# EEZ_CF-DIC_r3B7.net
KiCad netlist of a schematic drawn in EAGLE
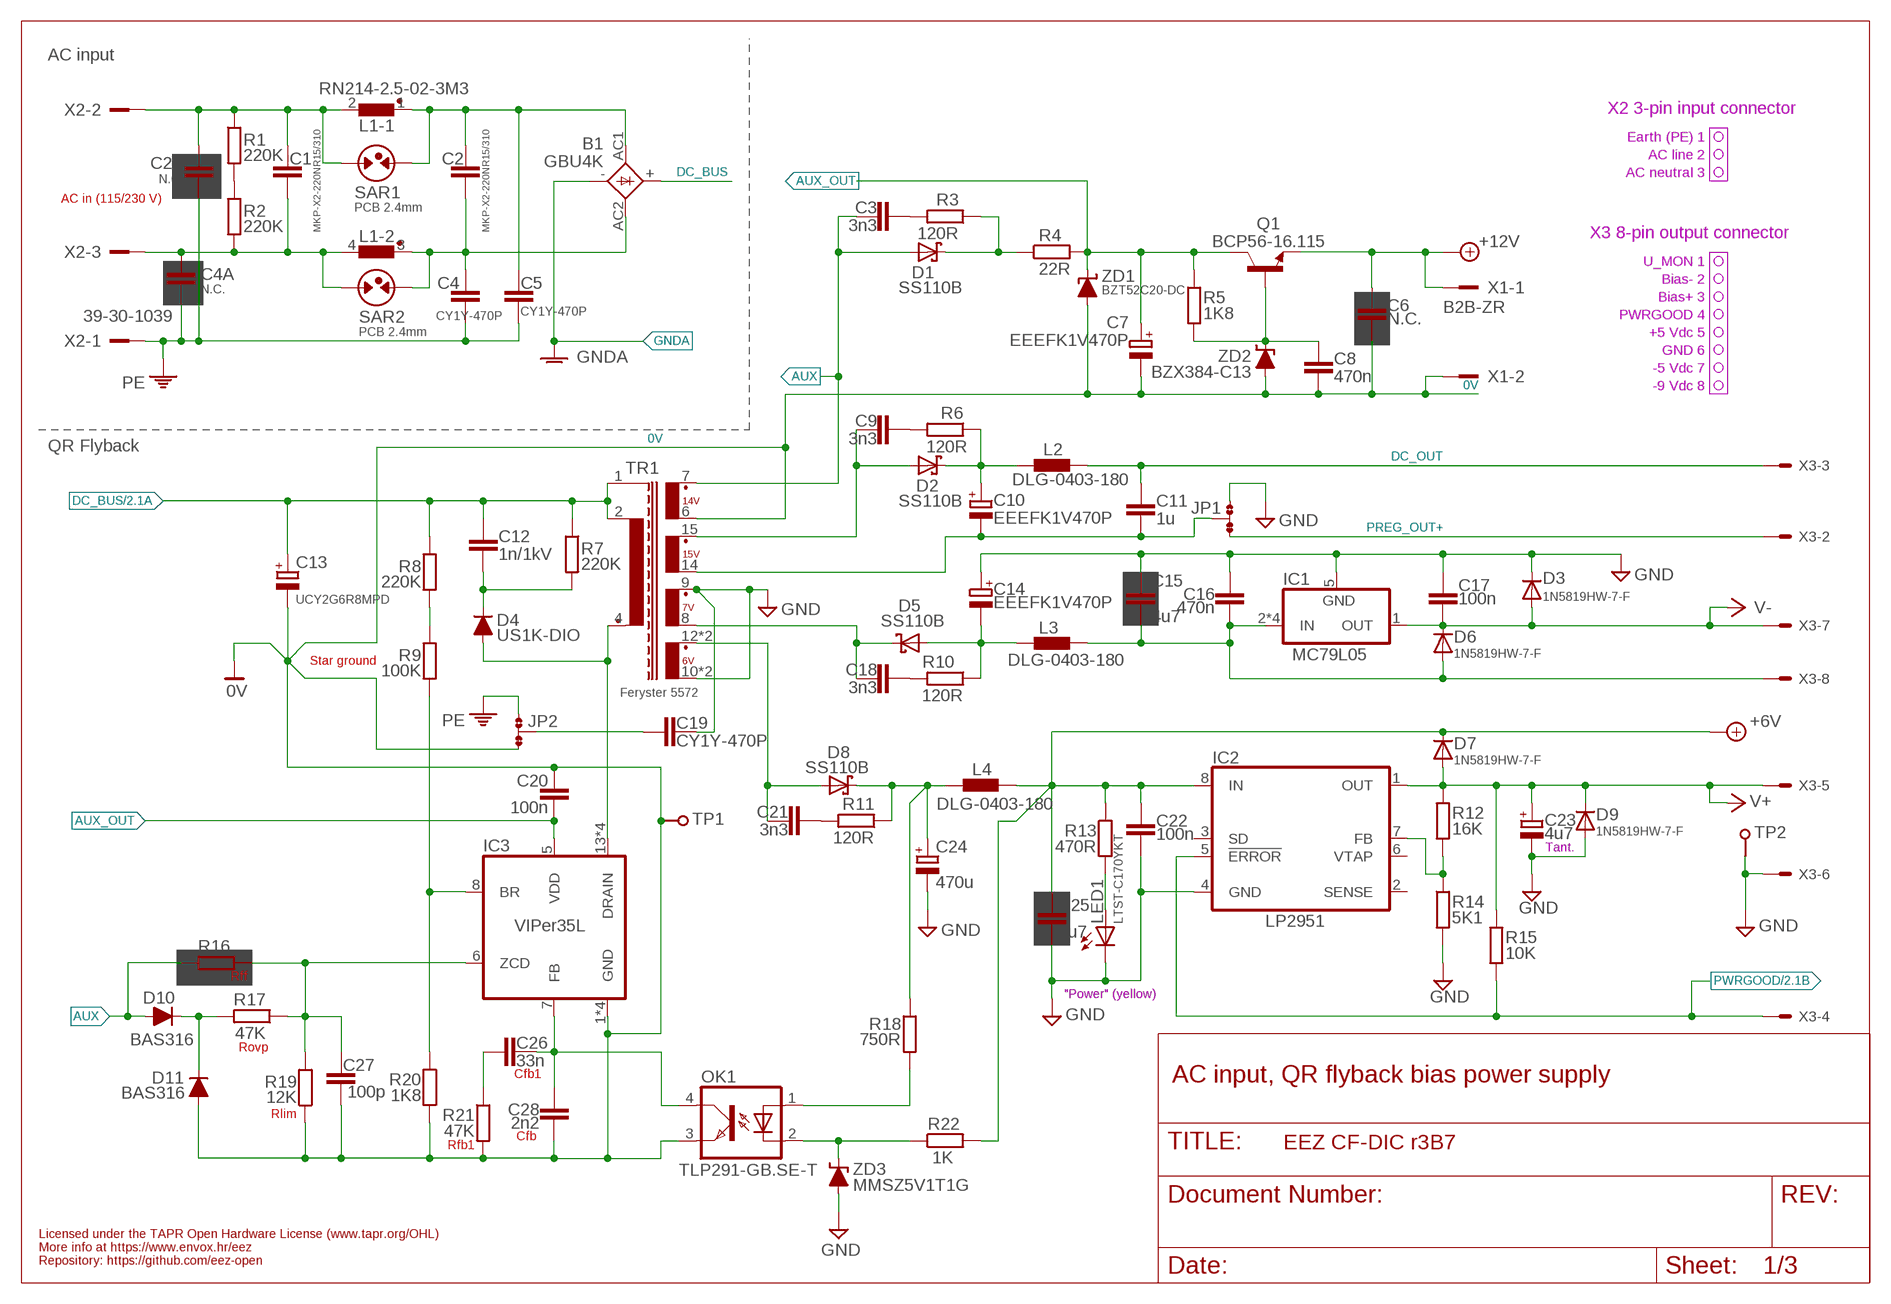
[diagram p0: schematic, sheet 1]
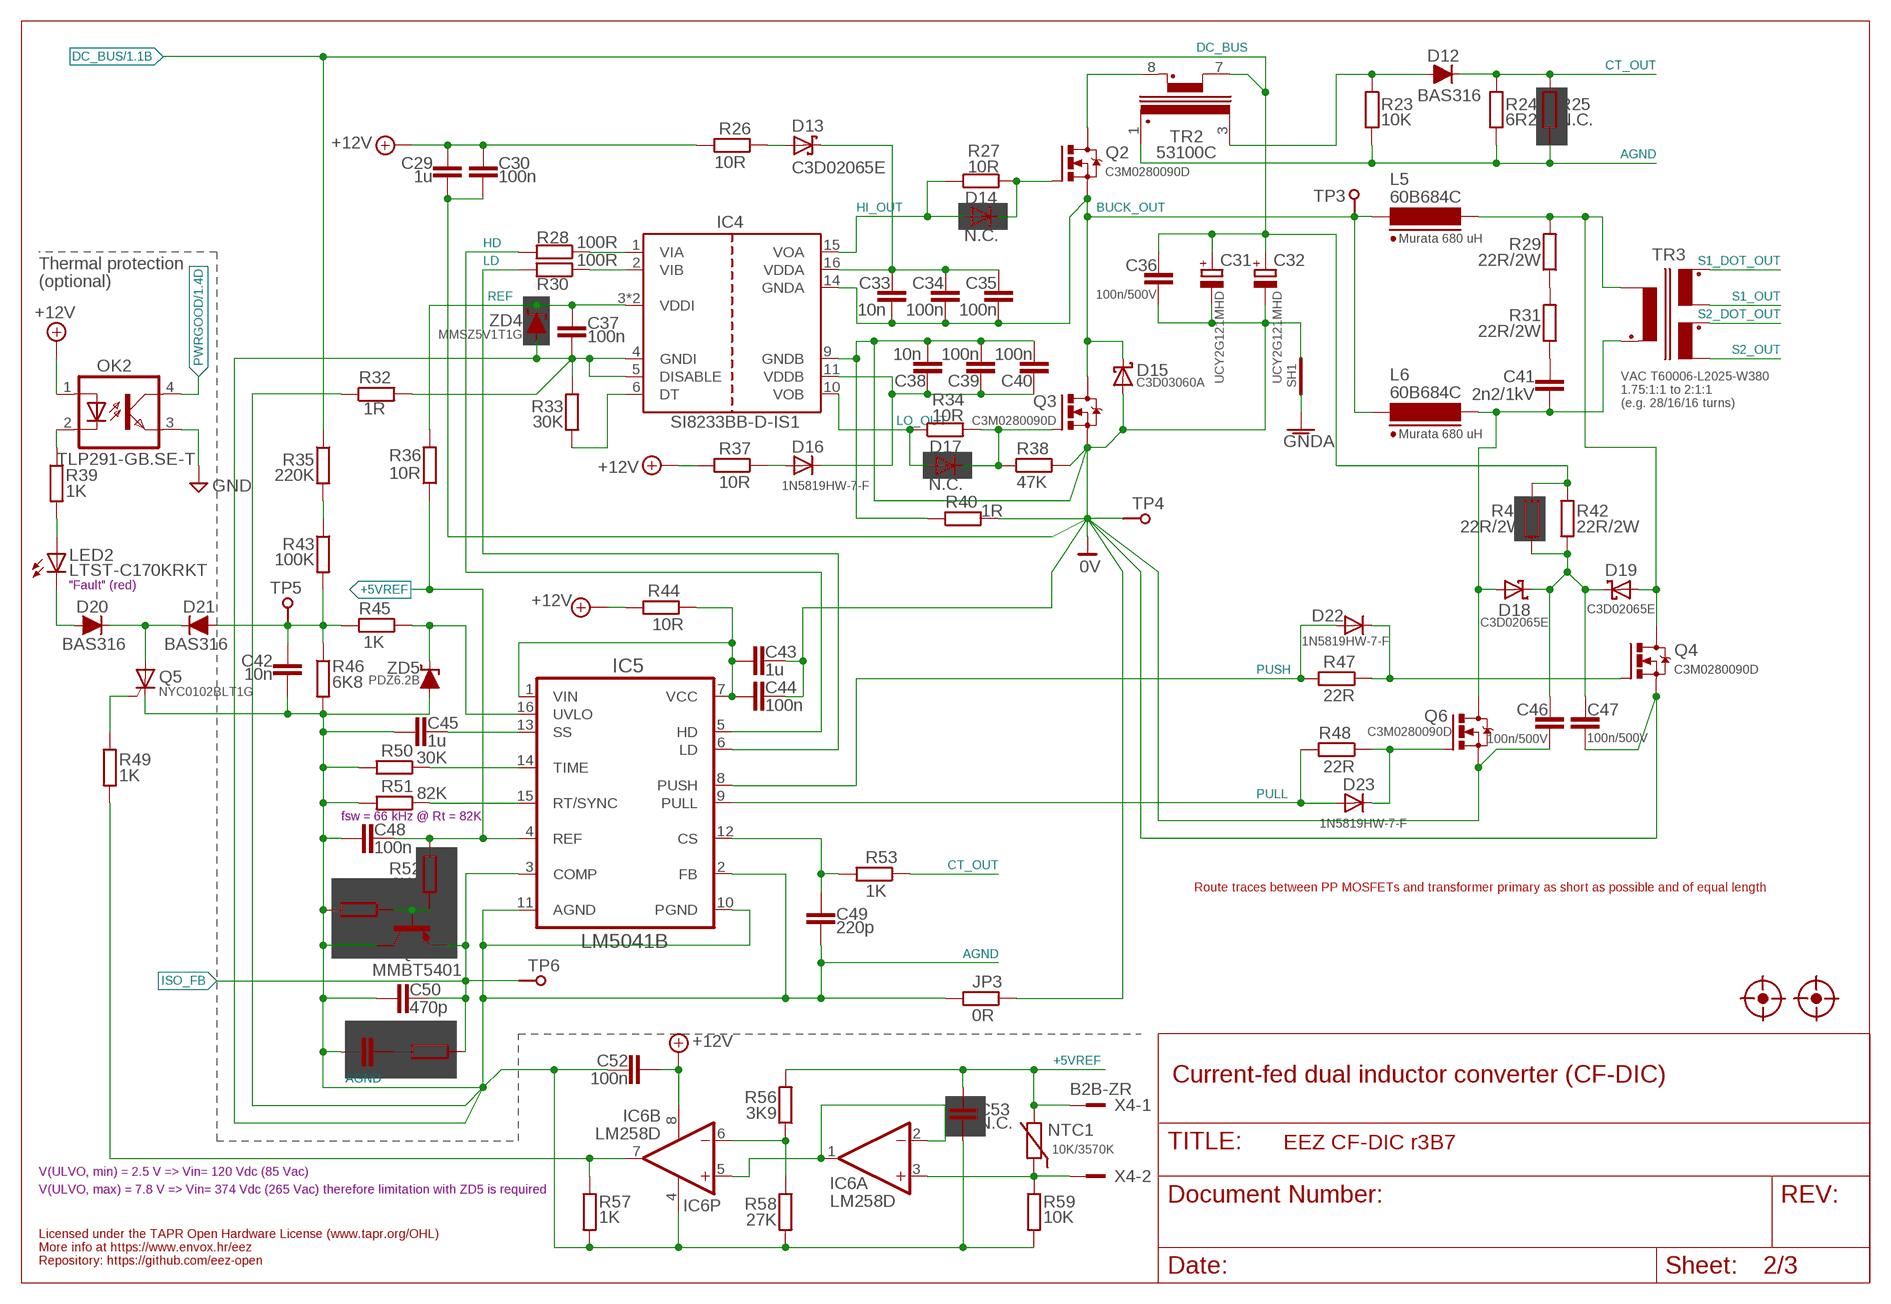
[diagram p1: schematic, sheet 2]
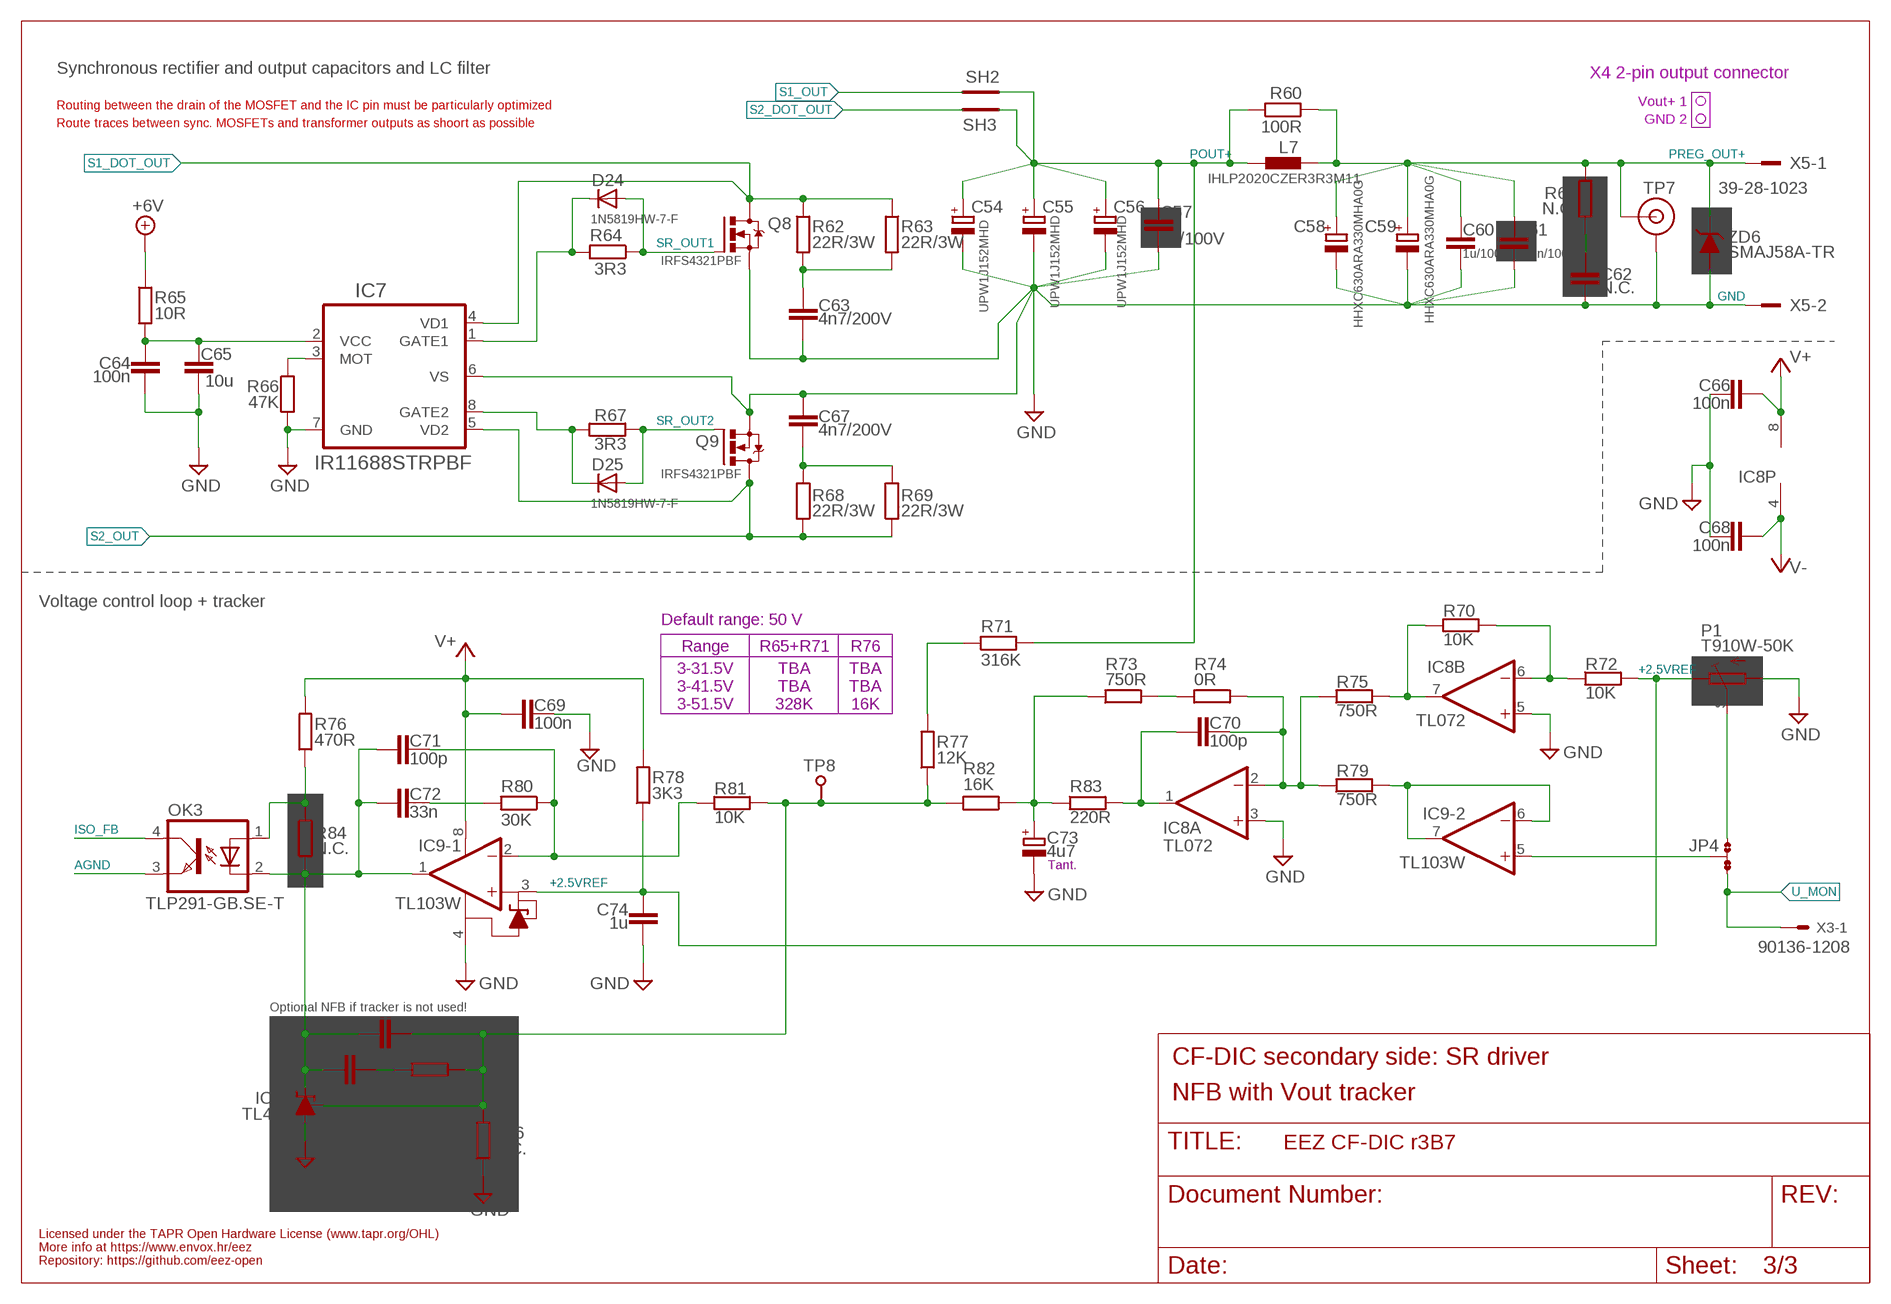
[diagram p2: schematic, sheet 3]

(export (version "E")
  (design (tool "Eeschema 10.0.6"))
  (components
    (comp (ref "C29")
      (value "1u")
      (footprint "eagle-import:C0805")
      (libsource (lib "eagle-import") (part "C-EUC0805"))
    )
    (comp (ref "C30")
      (value "100n")
      (footprint "eagle-import:C0603")
      (libsource (lib "eagle-import") (part "C-EUC0603"))
    )
    (comp (ref "C31")
      (value "UCY2G121MHD")
      (footprint "eagle-import:ECAP7.5_18")
      (libsource (lib "eagle-import") (part "ECAP7.5G_18MM"))
    )
    (comp (ref "C32")
      (value "UCY2G121MHD")
      (footprint "eagle-import:ECAP7.5_18")
      (libsource (lib "eagle-import") (part "ECAP7.5G_18MM"))
    )
    (comp (ref "C33")
      (value "10n")
      (footprint "eagle-import:C0603")
      (libsource (lib "eagle-import") (part "C-EUC0603"))
    )
    (comp (ref "C34")
      (value "100n")
      (footprint "eagle-import:C0603")
      (libsource (lib "eagle-import") (part "C-EUC0603"))
    )
    (comp (ref "C35")
      (value "100n")
      (footprint "eagle-import:C0603")
      (libsource (lib "eagle-import") (part "C-EUC0603"))
    )
    (comp (ref "C36")
      (value "100n/500V")
      (footprint "eagle-import:C1812")
      (libsource (lib "eagle-import") (part "C-EUC1812"))
    )
    (comp (ref "C37")
      (value "100n")
      (footprint "eagle-import:C0603")
      (libsource (lib "eagle-import") (part "C-EUC0603"))
    )
    (comp (ref "C38")
      (value "10n")
      (footprint "eagle-import:C0603")
      (libsource (lib "eagle-import") (part "C-EUC0603"))
    )
    (comp (ref "C39")
      (value "100n")
      (footprint "eagle-import:C0603")
      (libsource (lib "eagle-import") (part "C-EUC0603"))
    )
    (comp (ref "C40")
      (value "100n")
      (footprint "eagle-import:C0603")
      (libsource (lib "eagle-import") (part "C-EUC0603"))
    )
    (comp (ref "C41")
      (value "2n2/1kV")
      (footprint "eagle-import:C1210")
      (libsource (lib "eagle-import") (part "C-EUC1210"))
    )
    (comp (ref "C42")
      (value "10n")
      (footprint "eagle-import:C0603")
      (libsource (lib "eagle-import") (part "C-EUC0603"))
    )
    (comp (ref "C43")
      (value "1u")
      (footprint "eagle-import:C0805")
      (libsource (lib "eagle-import") (part "C-EUC0805"))
    )
    (comp (ref "C44")
      (value "100n")
      (footprint "eagle-import:C0603")
      (libsource (lib "eagle-import") (part "C-EUC0603"))
    )
    (comp (ref "C45")
      (value "1u")
      (footprint "eagle-import:C0805")
      (libsource (lib "eagle-import") (part "C-EUC0805"))
    )
    (comp (ref "C46")
      (value "100n/500V")
      (footprint "eagle-import:C1812")
      (libsource (lib "eagle-import") (part "C-EUC1812"))
    )
    (comp (ref "C47")
      (value "100n/500V")
      (footprint "eagle-import:C1812")
      (libsource (lib "eagle-import") (part "C-EUC1812"))
    )
    (comp (ref "C48")
      (value "100n")
      (footprint "eagle-import:C0603")
      (libsource (lib "eagle-import") (part "C-EUC0603"))
    )
    (comp (ref "C49")
      (value "220p")
      (footprint "eagle-import:C0805")
      (libsource (lib "eagle-import") (part "C-EUC0805"))
    )
    (comp (ref "C50")
      (value "470p")
      (footprint "eagle-import:C0805")
      (libsource (lib "eagle-import") (part "C-EUC0805"))
    )
    (comp (ref "C51")
      (value "N.C.")
      (footprint "eagle-import:C0805")
      (libsource (lib "eagle-import") (part "C-EUC0805"))
    )
    (comp (ref "C52")
      (value "100n")
      (footprint "eagle-import:C0603")
      (libsource (lib "eagle-import") (part "C-EUC0603"))
    )
    (comp (ref "C53")
      (value "N.C.")
      (footprint "eagle-import:C0603")
      (libsource (lib "eagle-import") (part "C-EUC0603"))
    )
    (comp (ref "D12")
      (value "BAS316")
      (footprint "eagle-import:SOD323-R")
      (libsource (lib "eagle-import") (part "DIODESOD323R"))
    )
    (comp (ref "D13")
      (value "C3D02065E")
      (footprint "eagle-import:TO252")
      (libsource (lib "eagle-import") (part "SCHOTTKY-SIC"))
    )
    (comp (ref "D14")
      (value "N.C.")
      (footprint "eagle-import:SOD323-W")
      (libsource (lib "eagle-import") (part "DIODE-SOD323-W"))
    )
    (comp (ref "D15")
      (value "C3D03060A")
      (footprint "eagle-import:TO220-2")
      (libsource (lib "eagle-import") (part "SCHOTTKY-TO220"))
    )
    (comp (ref "D16")
      (value "1N5819HW-7-F")
      (footprint "eagle-import:SOD323-W")
      (libsource (lib "eagle-import") (part "DIODE-SOD323-W"))
    )
    (comp (ref "D17")
      (value "N.C.")
      (footprint "eagle-import:SOD323-W")
      (libsource (lib "eagle-import") (part "DIODE-SOD323-W"))
    )
    (comp (ref "D18")
      (value "C3D02065E")
      (footprint "eagle-import:TO252")
      (libsource (lib "eagle-import") (part "SCHOTTKY-SIC"))
    )
    (comp (ref "D19")
      (value "C3D02065E")
      (footprint "eagle-import:TO252")
      (libsource (lib "eagle-import") (part "SCHOTTKY-SIC"))
    )
    (comp (ref "D20")
      (value "BAS316")
      (footprint "eagle-import:SOD323-R")
      (libsource (lib "eagle-import") (part "DIODESOD323R"))
    )
    (comp (ref "D21")
      (value "BAS316")
      (footprint "eagle-import:SOD323-R")
      (libsource (lib "eagle-import") (part "DIODESOD323R"))
    )
    (comp (ref "D22")
      (value "1N5819HW-7-F")
      (footprint "eagle-import:SOD323-W")
      (libsource (lib "eagle-import") (part "DIODE-SOD323-W"))
    )
    (comp (ref "D23")
      (value "1N5819HW-7-F")
      (footprint "eagle-import:SOD323-W")
      (libsource (lib "eagle-import") (part "DIODE-SOD323-W"))
    )
    (comp (ref "FM1")
      (value "FIDUCIAL_2")
      (footprint "eagle-import:FIDUCIAL_DUAL")
      (libsource (lib "eagle-import") (part "FIDUCIAL_2"))
    )
    (comp (ref "FM2")
      (value "FIDUCIAL_2")
      (footprint "eagle-import:FIDUCIAL_DUAL")
      (libsource (lib "eagle-import") (part "FIDUCIAL_2"))
    )
    (comp (ref "IC4")
      (value "SI8233BB-D-IS1")
      (footprint "eagle-import:SOIC-16")
      (libsource (lib "eagle-import") (part "SI8233"))
    )
    (comp (ref "IC5")
      (value "LM5041B")
      (footprint "eagle-import:MTC16")
      (fields (field (name "MANUFACTURER_PART_NUMBER") "lm5041mtcnopb"))
      (libsource (lib "eagle-import") (part "LM5041"))
    )
    (comp (ref "IC6")
      (value "LM258D")
      (footprint "eagle-import:SOIC127P600X173-8N")
      (libsource (lib "eagle-import") (part "TL072SOIC8"))
    )
    (comp (ref "JP3")
      (value "0R")
      (footprint "eagle-import:R0805")
      (libsource (lib "eagle-import") (part "R-EU_R0805"))
    )
    (comp (ref "L5")
      (value "60B684C")
      (footprint "eagle-import:MURATA_6000B")
      (libsource (lib "eagle-import") (part "EEZ_inductors_and_transformers_MURATA_6000B"))
    )
    (comp (ref "L6")
      (value "60B684C")
      (footprint "eagle-import:MURATA_6000B")
      (libsource (lib "eagle-import") (part "EEZ_inductors_and_transformers_MURATA_6000B"))
    )
    (comp (ref "LED2")
      (value "LTST-C170KRKT")
      (footprint "eagle-import:LED_0805")
      (libsource (lib "eagle-import") (part "LED0805"))
    )
    (comp (ref "NTC1")
      (value "10K/3570K")
      (footprint "eagle-import:R_0805")
      (libsource (lib "eagle-import") (part "NTCR_0805"))
    )
    (comp (ref "OK2")
      (value "TLP291-GB.SE-T")
      (footprint "eagle-import:SO4")
      (libsource (lib "eagle-import") (part "TLP291"))
    )
    (comp (ref "Q2")
      (value "C3M0280090D")
      (footprint "eagle-import:TO247BV")
      (libsource (lib "eagle-import") (part "IRFP240"))
    )
    (comp (ref "Q3")
      (value "C3M0280090D")
      (footprint "eagle-import:TO247BV")
      (libsource (lib "eagle-import") (part "IRFP240"))
    )
    (comp (ref "Q4")
      (value "C3M0280090D")
      (footprint "eagle-import:TO247BV")
      (libsource (lib "eagle-import") (part "IRFP240"))
    )
    (comp (ref "Q5")
      (value "NYC0102BLT1G")
      (footprint "eagle-import:SOT23")
      (libsource (lib "eagle-import") (part "NYC0102BLT1G"))
    )
    (comp (ref "Q6")
      (value "C3M0280090D")
      (footprint "eagle-import:TO247BV")
      (libsource (lib "eagle-import") (part "IRFP240"))
    )
    (comp (ref "Q7")
      (value "MMBT5401")
      (footprint "eagle-import:SOT23-BEC")
      (libsource (lib "eagle-import") (part "-PNP-SOT23-BECBC857B"))
    )
    (comp (ref "R23")
      (value "10K")
      (footprint "eagle-import:R0805")
      (libsource (lib "eagle-import") (part "R-EU_R0805"))
    )
    (comp (ref "R24")
      (value "6R2")
      (footprint "eagle-import:R0805")
      (libsource (lib "eagle-import") (part "R-EU_R0805"))
    )
    (comp (ref "R25")
      (value "N.C.")
      (footprint "eagle-import:R0805")
      (libsource (lib "eagle-import") (part "R-EU_R0805"))
    )
    (comp (ref "R26")
      (value "10R")
      (footprint "eagle-import:R0805")
      (libsource (lib "eagle-import") (part "R-EU_R0805"))
    )
    (comp (ref "R27")
      (value "10R")
      (footprint "eagle-import:R0805")
      (libsource (lib "eagle-import") (part "R-EU_R0805"))
    )
    (comp (ref "R28")
      (value "100R")
      (footprint "eagle-import:R0805")
      (libsource (lib "eagle-import") (part "R-EU_R0805"))
    )
    (comp (ref "R29")
      (value "22R/2W")
      (footprint "eagle-import:R2512")
      (libsource (lib "eagle-import") (part "R-EU_R2512"))
    )
    (comp (ref "R30")
      (value "100R")
      (footprint "eagle-import:R0805")
      (libsource (lib "eagle-import") (part "R-EU_R0805"))
    )
    (comp (ref "R31")
      (value "22R/2W")
      (footprint "eagle-import:R2512")
      (libsource (lib "eagle-import") (part "R-EU_R2512"))
    )
    (comp (ref "R32")
      (value "1R")
      (footprint "eagle-import:R0805")
      (libsource (lib "eagle-import") (part "R-EU_R0805"))
    )
    (comp (ref "R33")
      (value "30K")
      (footprint "eagle-import:R0805")
      (libsource (lib "eagle-import") (part "R-EU_R0805"))
    )
    (comp (ref "R34")
      (value "10R")
      (footprint "eagle-import:R0805")
      (libsource (lib "eagle-import") (part "R-EU_R0805"))
    )
    (comp (ref "R35")
      (value "220K")
      (footprint "eagle-import:R1206")
      (libsource (lib "eagle-import") (part "R-EU_R1206"))
    )
    (comp (ref "R36")
      (value "10R")
      (footprint "eagle-import:R0805")
      (libsource (lib "eagle-import") (part "R-EU_R0805"))
    )
    (comp (ref "R37")
      (value "10R")
      (footprint "eagle-import:R0805")
      (libsource (lib "eagle-import") (part "R-EU_R0805"))
    )
    (comp (ref "R38")
      (value "47K")
      (footprint "eagle-import:R0805")
      (libsource (lib "eagle-import") (part "R-EU_R0805"))
    )
    (comp (ref "R39")
      (value "1K")
      (footprint "eagle-import:R0805")
      (libsource (lib "eagle-import") (part "R-EU_R0805"))
    )
    (comp (ref "R40")
      (value "1R")
      (footprint "eagle-import:R0805")
      (libsource (lib "eagle-import") (part "R-EU_R0805"))
    )
    (comp (ref "R41")
      (value "22R/2W")
      (footprint "eagle-import:R2512")
      (libsource (lib "eagle-import") (part "R-EU_R2512"))
    )
    (comp (ref "R42")
      (value "22R/2W")
      (footprint "eagle-import:R2512")
      (libsource (lib "eagle-import") (part "R-EU_R2512"))
    )
    (comp (ref "R43")
      (value "100K")
      (footprint "eagle-import:R0805")
      (libsource (lib "eagle-import") (part "R-EU_R0805"))
    )
    (comp (ref "R44")
      (value "10R")
      (footprint "eagle-import:R0805")
      (libsource (lib "eagle-import") (part "R-EU_R0805"))
    )
    (comp (ref "R45")
      (value "1K")
      (footprint "eagle-import:R0805")
      (libsource (lib "eagle-import") (part "R-EU_R0805"))
    )
    (comp (ref "R46")
      (value "6K8")
      (footprint "eagle-import:R0805")
      (libsource (lib "eagle-import") (part "R-EU_R0805"))
    )
    (comp (ref "R47")
      (value "22R")
      (footprint "eagle-import:R0805")
      (libsource (lib "eagle-import") (part "R-EU_R0805"))
    )
    (comp (ref "R48")
      (value "22R")
      (footprint "eagle-import:R0805")
      (libsource (lib "eagle-import") (part "R-EU_R0805"))
    )
    (comp (ref "R49")
      (value "1K")
      (footprint "eagle-import:R0805")
      (libsource (lib "eagle-import") (part "R-EU_R0805"))
    )
    (comp (ref "R50")
      (value "30K")
      (footprint "eagle-import:R0805")
      (libsource (lib "eagle-import") (part "R-EU_R0805"))
    )
    (comp (ref "R51")
      (value "82K")
      (footprint "eagle-import:R0805")
      (libsource (lib "eagle-import") (part "R-EU_R0805"))
    )
    (comp (ref "R52")
      (value "6K8")
      (footprint "eagle-import:R0805")
      (libsource (lib "eagle-import") (part "R-EU_R0805"))
    )
    (comp (ref "R53")
      (value "1K")
      (footprint "eagle-import:R0805")
      (libsource (lib "eagle-import") (part "R-EU_R0805"))
    )
    (comp (ref "R54")
      (value "6K8")
      (footprint "eagle-import:R0805")
      (libsource (lib "eagle-import") (part "R-EU_R0805"))
    )
    (comp (ref "R55")
      (value "N.C.")
      (footprint "eagle-import:R0805")
      (libsource (lib "eagle-import") (part "R-EU_R0805"))
    )
    (comp (ref "R56")
      (value "3K9")
      (footprint "eagle-import:R0805")
      (libsource (lib "eagle-import") (part "R-EU_R0805"))
    )
    (comp (ref "R57")
      (value "1K")
      (footprint "eagle-import:R0805")
      (libsource (lib "eagle-import") (part "R-EU_R0805"))
    )
    (comp (ref "R58")
      (value "27K")
      (footprint "eagle-import:R0805")
      (libsource (lib "eagle-import") (part "R-EU_R0805"))
    )
    (comp (ref "R59")
      (value "10K")
      (footprint "eagle-import:R0805")
      (libsource (lib "eagle-import") (part "R-EU_R0805"))
    )
    (comp (ref "SH1")
      (value "SHORTNOHOLE")
      (footprint "eagle-import:SHORT_NOHOLE")
      (libsource (lib "eagle-import") (part "SHORTNOHOLE"))
    )
    (comp (ref "TP3")
      (value "PCB_TEST_TABSHIELD")
      (footprint "eagle-import:PCB_SHIELD_TAB")
      (libsource (lib "eagle-import") (part "PCB_TEST_TABSHIELD"))
    )
    (comp (ref "TP4")
      (value "PCB_TEST_TABSHIELD")
      (footprint "eagle-import:PCB_SHIELD_TAB")
      (libsource (lib "eagle-import") (part "PCB_TEST_TABSHIELD"))
    )
    (comp (ref "TP5")
      (value "PCB_TEST_TABSHIELD")
      (footprint "eagle-import:PCB_SHIELD_TAB")
      (libsource (lib "eagle-import") (part "PCB_TEST_TABSHIELD"))
    )
    (comp (ref "TP6")
      (value "PCB_TEST_TABSHIELD")
      (footprint "eagle-import:PCB_SHIELD_TAB")
      (libsource (lib "eagle-import") (part "PCB_TEST_TABSHIELD"))
    )
    (comp (ref "TR2")
      (value "53100C")
      (footprint "eagle-import:MURATA_5300")
      (libsource (lib "eagle-import") (part "MURATA_5300"))
    )
    (comp (ref "TR3")
      (value "VAC T60006-L2025-W380")
      (footprint "eagle-import:VAC_DUAL_SEC")
      (libsource (lib "eagle-import") (part "PCB_TRAFO_FLYBACK2-VAC"))
    )
    (comp (ref "X4")
      (value "B2B-ZR")
      (footprint "eagle-import:B2B-ZR")
      (libsource (lib "eagle-import") (part "B2B-ZR"))
    )
    (comp (ref "ZD4")
      (value "MMSZ5V1T1G")
      (footprint "eagle-import:SOD323-W")
      (libsource (lib "eagle-import") (part "ZENER-DIODESOD323"))
    )
    (comp (ref "ZD5")
      (value "PDZ6.2B")
      (footprint "eagle-import:SOD323-W")
      (libsource (lib "eagle-import") (part "ZENER-DIODESOD323"))
    )
    (comp (ref "C54")
      (value "UPW1J152MHD")
      (footprint "eagle-import:ECAP7.5_18")
      (libsource (lib "eagle-import") (part "ECAP7.5G_18MM"))
    )
    (comp (ref "C55")
      (value "UPW1J152MHD")
      (footprint "eagle-import:ECAP7.5_18")
      (libsource (lib "eagle-import") (part "ECAP7.5G_18MM"))
    )
    (comp (ref "C56")
      (value "UPW1J152MHD")
      (footprint "eagle-import:ECAP7.5_18")
      (libsource (lib "eagle-import") (part "ECAP7.5G_18MM"))
    )
    (comp (ref "C57")
      (value "1u/100V")
      (footprint "eagle-import:C1206")
      (libsource (lib "eagle-import") (part "C-EUC1206"))
    )
    (comp (ref "C58")
      (value "HHXC630ARA330MHA0G ")
      (footprint "eagle-import:CAPAE830X1050N")
      (fields
        (field (name "MPN") "EEE-FK1J470P")
        (field (name "TOLERANCE") "±20 %")
        (field (name "MPN_1") "EEE-FK1J470P")
        (field (name "OC_FARNELL") "9696032  ")
        (field (name "OC_NEWARK") "96K9403")
        (field (name "PACKAGE") "CASE-F")
        (field (name "SUPPLIER") "PANASONIC")
        (field (name "TOLERANCE_1") "±20 %")
        (field (name "VOLTAGERATING") "63 V")
      )
      (libsource (lib "eagle-import") (part "EEE--CASE-FFK1J470P"))
    )
    (comp (ref "C59")
      (value "HHXC630ARA330MHA0G")
      (footprint "eagle-import:CAPAE830X1050N")
      (fields (field (name "MPN") "EEE-FK1J470P") (field (name "TOLERANCE") "±20 %"))
      (libsource (lib "eagle-import") (part "EEE--CASE-FFK1J470P"))
    )
    (comp (ref "C60")
      (value "1u/100V")
      (footprint "eagle-import:C1206")
      (libsource (lib "eagle-import") (part "C-EUC1206"))
    )
    (comp (ref "C61")
      (value "100n/100V")
      (footprint "eagle-import:C0805")
      (libsource (lib "eagle-import") (part "C-EUC0805"))
    )
    (comp (ref "C62")
      (value "N.C.")
      (footprint "eagle-import:C1206")
      (libsource (lib "eagle-import") (part "C-EUC1206"))
    )
    (comp (ref "C63")
      (value "4n7/200V")
      (footprint "eagle-import:C1206")
      (libsource (lib "eagle-import") (part "C-EUC1206"))
    )
    (comp (ref "C64")
      (value "100n")
      (footprint "eagle-import:C0603")
      (libsource (lib "eagle-import") (part "C-EUC0603"))
    )
    (comp (ref "C65")
      (value "10u")
      (footprint "eagle-import:C1210")
      (libsource (lib "eagle-import") (part "C-EUC1210"))
    )
    (comp (ref "C66")
      (value "100n")
      (footprint "eagle-import:C0603")
      (libsource (lib "eagle-import") (part "C-EUC0603"))
    )
    (comp (ref "C67")
      (value "4n7/200V")
      (footprint "eagle-import:C1206")
      (libsource (lib "eagle-import") (part "C-EUC1206"))
    )
    (comp (ref "C68")
      (value "100n")
      (footprint "eagle-import:C0603")
      (libsource (lib "eagle-import") (part "C-EUC0603"))
    )
    (comp (ref "C69")
      (value "100n")
      (footprint "eagle-import:C0603")
      (libsource (lib "eagle-import") (part "C-EUC0603"))
    )
    (comp (ref "C70")
      (value "100p")
      (footprint "eagle-import:C0805")
      (libsource (lib "eagle-import") (part "C-EUC0805"))
    )
    (comp (ref "C71")
      (value "100p")
      (footprint "eagle-import:C0805")
      (libsource (lib "eagle-import") (part "C-EUC0805"))
    )
    (comp (ref "C72")
      (value "33n")
      (footprint "eagle-import:C0805")
      (libsource (lib "eagle-import") (part "C-EUC0805"))
    )
    (comp (ref "C73")
      (value "4u7")
      (footprint "eagle-import:EC1206")
      (libsource (lib "eagle-import") (part "ECAP1206"))
    )
    (comp (ref "C74")
      (value "1u")
      (footprint "eagle-import:C0805")
      (libsource (lib "eagle-import") (part "C-EUC0805"))
    )
    (comp (ref "C75")
      (value "N.C.")
      (footprint "eagle-import:C0805")
      (libsource (lib "eagle-import") (part "C-EUC0805"))
    )
    (comp (ref "C76")
      (value "N.C.")
      (footprint "eagle-import:C0805")
      (libsource (lib "eagle-import") (part "C-EUC0805"))
    )
    (comp (ref "D24")
      (value "1N5819HW-7-F")
      (footprint "eagle-import:SOD323-W")
      (libsource (lib "eagle-import") (part "DIODE-SOD323-W"))
    )
    (comp (ref "D25")
      (value "1N5819HW-7-F")
      (footprint "eagle-import:SOD323-W")
      (libsource (lib "eagle-import") (part "DIODE-SOD323-W"))
    )
    (comp (ref "IC7")
      (value "IR11688STRPBF")
      (footprint "eagle-import:SO8")
      (libsource (lib "eagle-import") (part "IR11688"))
    )
    (comp (ref "IC8")
      (value "TL072")
      (footprint "eagle-import:SOIC127P600X173-8N")
      (libsource (lib "eagle-import") (part "TL072SOIC8"))
    )
    (comp (ref "IC9")
      (value "TL103W")
      (footprint "eagle-import:SOIC127P600X173-8N")
      (libsource (lib "eagle-import") (part "TL103W"))
    )
    (comp (ref "IC10")
      (value "TL431")
      (footprint "eagle-import:SOT103P240X110-3N")
      (libsource (lib "eagle-import") (part "TL431"))
    )
    (comp (ref "JP4")
      (value "JP3-CUT")
      (footprint "eagle-import:JP3-CUT")
      (libsource (lib "eagle-import") (part "JP3-CUT"))
    )
    (comp (ref "L7")
      (value "IHLP2020CZER3R3M11")
      (footprint "eagle-import:IHLP-2020BZ-11")
      (libsource (lib "eagle-import") (part "EEZ_inductors_and_transformers_IHLP-2020BZ-11"))
    )
    (comp (ref "OK3")
      (value "TLP291-GB.SE-T")
      (footprint "eagle-import:SO4")
      (libsource (lib "eagle-import") (part "TLP291"))
    )
    (comp (ref "P1")
      (value "T910W-50K")
      (footprint "eagle-import:S64W")
      (libsource (lib "eagle-import") (part "TPOT-S64W"))
    )
    (comp (ref "Q8")
      (value "IRFS4321PBF")
      (footprint "eagle-import:TO263")
      (libsource (lib "eagle-import") (part "N-MOSFETTO263"))
    )
    (comp (ref "Q9")
      (value "IRFS4321PBF")
      (footprint "eagle-import:TO263")
      (libsource (lib "eagle-import") (part "N-MOSFETTO263"))
    )
    (comp (ref "R60")
      (value "100R")
      (footprint "eagle-import:R0805")
      (libsource (lib "eagle-import") (part "R-EU_R0805"))
    )
    (comp (ref "R61")
      (value "N.C.")
      (footprint "eagle-import:R1210")
      (libsource (lib "eagle-import") (part "R-EU_R1210"))
    )
    (comp (ref "R62")
      (value "22R/3W")
      (footprint "eagle-import:R2512")
      (libsource (lib "eagle-import") (part "R-EU_R2512"))
    )
    (comp (ref "R63")
      (value "22R/3W")
      (footprint "eagle-import:R2512")
      (libsource (lib "eagle-import") (part "R-EU_R2512"))
    )
    (comp (ref "R64")
      (value "3R3")
      (footprint "eagle-import:R0805")
      (libsource (lib "eagle-import") (part "R-EU_R0805"))
    )
    (comp (ref "R65")
      (value "10R")
      (footprint "eagle-import:R0805")
      (libsource (lib "eagle-import") (part "R-EU_R0805"))
    )
    (comp (ref "R66")
      (value "47K")
      (footprint "eagle-import:R0805")
      (libsource (lib "eagle-import") (part "R-EU_R0805"))
    )
    (comp (ref "R67")
      (value "3R3")
      (footprint "eagle-import:R0805")
      (libsource (lib "eagle-import") (part "R-EU_R0805"))
    )
    (comp (ref "R68")
      (value "22R/3W")
      (footprint "eagle-import:R2512")
      (libsource (lib "eagle-import") (part "R-EU_R2512"))
    )
    (comp (ref "R69")
      (value "22R/3W")
      (footprint "eagle-import:R2512")
      (libsource (lib "eagle-import") (part "R-EU_R2512"))
    )
    (comp (ref "R70")
      (value "10K")
      (footprint "eagle-import:R0805")
      (libsource (lib "eagle-import") (part "R-EU_R0805"))
    )
    (comp (ref "R71")
      (value "316K")
      (footprint "eagle-import:R0805")
      (libsource (lib "eagle-import") (part "R-EU_R0805"))
    )
    (comp (ref "R72")
      (value "10K")
      (footprint "eagle-import:R0805")
      (libsource (lib "eagle-import") (part "R-EU_R0805"))
    )
    (comp (ref "R73")
      (value "750R")
      (footprint "eagle-import:R0805")
      (libsource (lib "eagle-import") (part "R-EU_R0805"))
    )
    (comp (ref "R74")
      (value "0R")
      (footprint "eagle-import:R0805")
      (libsource (lib "eagle-import") (part "R-EU_R0805"))
    )
    (comp (ref "R75")
      (value "750R")
      (footprint "eagle-import:R0805")
      (libsource (lib "eagle-import") (part "R-EU_R0805"))
    )
    (comp (ref "R76")
      (value "470R")
      (footprint "eagle-import:R0805")
      (libsource (lib "eagle-import") (part "R-EU_R0805"))
    )
    (comp (ref "R77")
      (value "12K")
      (footprint "eagle-import:R0805")
      (libsource (lib "eagle-import") (part "R-EU_R0805"))
    )
    (comp (ref "R78")
      (value "3K3")
      (footprint "eagle-import:R0805")
      (libsource (lib "eagle-import") (part "R-EU_R0805"))
    )
    (comp (ref "R79")
      (value "750R")
      (footprint "eagle-import:R0805")
      (libsource (lib "eagle-import") (part "R-EU_R0805"))
    )
    (comp (ref "R80")
      (value "30K")
      (footprint "eagle-import:R0805")
      (libsource (lib "eagle-import") (part "R-EU_R0805"))
    )
    (comp (ref "R81")
      (value "10K")
      (footprint "eagle-import:R0805")
      (libsource (lib "eagle-import") (part "R-EU_R0805"))
    )
    (comp (ref "R82")
      (value "16K")
      (footprint "eagle-import:R0805")
      (libsource (lib "eagle-import") (part "R-EU_R0805"))
    )
    (comp (ref "R83")
      (value "220R")
      (footprint "eagle-import:R0805")
      (libsource (lib "eagle-import") (part "R-EU_R0805"))
    )
    (comp (ref "R84")
      (value "N.C.")
      (footprint "eagle-import:R0805")
      (libsource (lib "eagle-import") (part "R-EU_R0805"))
    )
    (comp (ref "R85")
      (value "N.C.")
      (footprint "eagle-import:R0805")
      (libsource (lib "eagle-import") (part "R-EU_R0805"))
    )
    (comp (ref "R86")
      (value "N.C.")
      (footprint "eagle-import:R0805")
      (libsource (lib "eagle-import") (part "R-EU_R0805"))
    )
    (comp (ref "SH2")
      (value "SHORTNOHOLE")
      (footprint "eagle-import:SHORT_NOHOLE")
      (libsource (lib "eagle-import") (part "SHORTNOHOLE"))
    )
    (comp (ref "SH3")
      (value "SHORTNOHOLE")
      (footprint "eagle-import:SHORT_NOHOLE")
      (libsource (lib "eagle-import") (part "SHORTNOHOLE"))
    )
    (comp (ref "TP7")
      (value "TEST_POINT-2")
      (footprint "eagle-import:TP_1.1MM_2")
      (libsource (lib "eagle-import") (part "TEST_POINT-2"))
    )
    (comp (ref "TP8")
      (value "PCB_TEST_TABSHIELD")
      (footprint "eagle-import:PCB_SHIELD_TAB")
      (libsource (lib "eagle-import") (part "PCB_TEST_TABSHIELD"))
    )
    (comp (ref "X3")
      (value "90136-1208")
      (footprint "eagle-import:70543-08")
      (libsource (lib "eagle-import") (part "C-GRID-08-70543"))
    )
    (comp (ref "X5")
      (value "39-28-1023")
      (footprint "eagle-import:MINIFIT_5566-02A")
      (libsource (lib "eagle-import") (part "MINIFIT_5566-02A"))
    )
    (comp (ref "ZD6")
      (value "SMAJ58A-TR")
      (footprint "eagle-import:DO214AC")
      (libsource (lib "eagle-import") (part "PSMAXX"))
    )
    (comp (ref "B1")
      (value "GBU4K")
      (footprint "eagle-import:GBU4K_CRE")
      (libsource (lib "eagle-import") (part "BRIDGE-CREEPAGE"))
    )
    (comp (ref "C1")
      (value "MKP-X2-220NR15/310")
      (footprint "eagle-import:C150-072X183")
      (libsource (lib "eagle-import") (part "C-EU150-072X183"))
    )
    (comp (ref "C2")
      (value "MKP-X2-220NR15/310")
      (footprint "eagle-import:C150-072X183")
      (libsource (lib "eagle-import") (part "C-EU150-072X183"))
    )
    (comp (ref "C2A")
      (value "N.C.")
      (footprint "eagle-import:CY075-032X103")
      (libsource (lib "eagle-import") (part "C-EUCY"))
    )
    (comp (ref "C3")
      (value "3n3")
      (footprint "eagle-import:C0805")
      (libsource (lib "eagle-import") (part "C-EUC0805"))
    )
    (comp (ref "C4")
      (value "CY1Y-470P")
      (footprint "eagle-import:CY075-032X103")
      (libsource (lib "eagle-import") (part "C-EUCY"))
    )
    (comp (ref "C4A")
      (value "N.C.")
      (footprint "eagle-import:CY075-032X103")
      (libsource (lib "eagle-import") (part "C-EUCY"))
    )
    (comp (ref "C5")
      (value "CY1Y-470P")
      (footprint "eagle-import:CY075-032X103")
      (libsource (lib "eagle-import") (part "C-EUCY"))
    )
    (comp (ref "C6")
      (value "N.C.")
      (footprint "eagle-import:C0603")
      (libsource (lib "eagle-import") (part "C-EUC0603"))
    )
    (comp (ref "C7")
      (value "EEEFK1V470P")
      (footprint "eagle-import:CAPAE660X610N")
      (libsource (lib "eagle-import") (part "ECAPPANASONIC_H"))
    )
    (comp (ref "C8")
      (value "470n")
      (footprint "eagle-import:C0805")
      (libsource (lib "eagle-import") (part "C-EUC0805"))
    )
    (comp (ref "C9")
      (value "3n3")
      (footprint "eagle-import:C0805")
      (libsource (lib "eagle-import") (part "C-EUC0805"))
    )
    (comp (ref "C10")
      (value "EEEFK1V470P")
      (footprint "eagle-import:CAPAE660X610N")
      (libsource (lib "eagle-import") (part "ECAPPANASONIC_H"))
    )
    (comp (ref "C11")
      (value "1u")
      (footprint "eagle-import:C0805")
      (libsource (lib "eagle-import") (part "C-EUC0805"))
    )
    (comp (ref "C12")
      (value "1n/1kV")
      (footprint "eagle-import:C1210")
      (libsource (lib "eagle-import") (part "C-EUC1210"))
    )
    (comp (ref "C13")
      (value "UCY2G6R8MPD")
      (footprint "eagle-import:ECAP5_10.5")
      (libsource (lib "eagle-import") (part "ECAP5G_10.5MM"))
    )
    (comp (ref "C14")
      (value "EEEFK1V470P")
      (footprint "eagle-import:CAPAE660X610N")
      (libsource (lib "eagle-import") (part "ECAPPANASONIC_H"))
    )
    (comp (ref "C15")
      (value "4u7")
      (footprint "eagle-import:C1206")
      (libsource (lib "eagle-import") (part "C-EUC1206"))
    )
    (comp (ref "C16")
      (value "470n")
      (footprint "eagle-import:C0805")
      (libsource (lib "eagle-import") (part "C-EUC0805"))
    )
    (comp (ref "C17")
      (value "100n")
      (footprint "eagle-import:C0603")
      (libsource (lib "eagle-import") (part "C-EUC0603"))
    )
    (comp (ref "C18")
      (value "3n3")
      (footprint "eagle-import:C0805")
      (libsource (lib "eagle-import") (part "C-EUC0805"))
    )
    (comp (ref "C19")
      (value "CY1Y-470P")
      (footprint "eagle-import:CY075-032X103")
      (libsource (lib "eagle-import") (part "C-EUCY"))
    )
    (comp (ref "C20")
      (value "100n")
      (footprint "eagle-import:C0603")
      (libsource (lib "eagle-import") (part "C-EUC0603"))
    )
    (comp (ref "C21")
      (value "3n3")
      (footprint "eagle-import:C0805")
      (libsource (lib "eagle-import") (part "C-EUC0805"))
    )
    (comp (ref "C22")
      (value "100n")
      (footprint "eagle-import:C0603")
      (libsource (lib "eagle-import") (part "C-EUC0603"))
    )
    (comp (ref "C23")
      (value "4u7")
      (footprint "eagle-import:EC1206")
      (libsource (lib "eagle-import") (part "ECAP1206"))
    )
    (comp (ref "C24")
      (value "470u")
      (footprint "eagle-import:ECAP5_10.5")
      (libsource (lib "eagle-import") (part "ECAP5G_10.5MM"))
    )
    (comp (ref "C25")
      (value "4u7")
      (footprint "eagle-import:C1206")
      (libsource (lib "eagle-import") (part "C-EUC1206"))
    )
    (comp (ref "C26")
      (value "33n")
      (footprint "eagle-import:C0805")
      (libsource (lib "eagle-import") (part "C-EUC0805"))
    )
    (comp (ref "C27")
      (value "100p")
      (footprint "eagle-import:C0805")
      (libsource (lib "eagle-import") (part "C-EUC0805"))
    )
    (comp (ref "C28")
      (value "2n2")
      (footprint "eagle-import:C0805")
      (libsource (lib "eagle-import") (part "C-EUC0805"))
    )
    (comp (ref "D1")
      (value "SS110B")
      (footprint "eagle-import:SMB")
      (libsource (lib "eagle-import") (part "SCHOTTKYSMB"))
    )
    (comp (ref "D2")
      (value "SS110B")
      (footprint "eagle-import:SMB")
      (libsource (lib "eagle-import") (part "SCHOTTKYSMB"))
    )
    (comp (ref "D3")
      (value "1N5819HW-7-F")
      (footprint "eagle-import:SOD323-W")
      (libsource (lib "eagle-import") (part "DIODE-SOD323-W"))
    )
    (comp (ref "D4")
      (value "US1K-DIO")
      (footprint "eagle-import:DO214AA")
      (libsource (lib "eagle-import") (part "DIODEDO214AA"))
    )
    (comp (ref "D5")
      (value "SS110B")
      (footprint "eagle-import:SMB")
      (libsource (lib "eagle-import") (part "SCHOTTKYSMB"))
    )
    (comp (ref "D6")
      (value "1N5819HW-7-F")
      (footprint "eagle-import:SOD323-W")
      (libsource (lib "eagle-import") (part "DIODE-SOD323-W"))
    )
    (comp (ref "D7")
      (value "1N5819HW-7-F")
      (footprint "eagle-import:SOD323-W")
      (libsource (lib "eagle-import") (part "DIODE-SOD323-W"))
    )
    (comp (ref "D8")
      (value "SS110B")
      (footprint "eagle-import:SMB")
      (libsource (lib "eagle-import") (part "SCHOTTKYSMB"))
    )
    (comp (ref "D9")
      (value "1N5819HW-7-F")
      (footprint "eagle-import:SOD323-W")
      (libsource (lib "eagle-import") (part "DIODE-SOD323-W"))
    )
    (comp (ref "D10")
      (value "BAS316")
      (footprint "eagle-import:SOD323-R")
      (libsource (lib "eagle-import") (part "DIODESOD323R"))
    )
    (comp (ref "D11")
      (value "BAS316")
      (footprint "eagle-import:SOD323-R")
      (libsource (lib "eagle-import") (part "DIODESOD323R"))
    )
    (comp (ref "IC1")
      (value "MC79L05")
      (footprint "eagle-import:SOIC127P600X173-8N")
      (libsource (lib "eagle-import") (part "MC79LXXSOIC"))
    )
    (comp (ref "IC2")
      (value "LP2951")
      (footprint "eagle-import:SOIC127P600X175-8N")
      (libsource (lib "eagle-import") (part "LP2951SO8"))
    )
    (comp (ref "IC3")
      (value "VIPer35L")
      (footprint "eagle-import:SOIC-16")
      (libsource (lib "eagle-import") (part "VIPER35"))
    )
    (comp (ref "JP1")
      (value "JP3-CUT")
      (footprint "eagle-import:JP3-CUT")
      (libsource (lib "eagle-import") (part "JP3-CUT"))
    )
    (comp (ref "JP2")
      (value "JP3-CUT")
      (footprint "eagle-import:JP3-CUT")
      (libsource (lib "eagle-import") (part "JP3-CUT"))
    )
    (comp (ref "L1")
      (value "RN214-2.5-02-3M3")
      (footprint "eagle-import:RN214")
      (fields (field (name "FARNELL") "1191518"))
      (libsource (lib "eagle-import") (part "EEZ_inductors_and_transformers_RN214"))
    )
    (comp (ref "L2")
      (value "DLG-0403-180")
      (footprint "eagle-import:DE0403")
      (libsource (lib "eagle-import") (part "EEZ_inductors_and_transformers_DE0403"))
    )
    (comp (ref "L3")
      (value "DLG-0403-180")
      (footprint "eagle-import:DE0403")
      (libsource (lib "eagle-import") (part "EEZ_inductors_and_transformers_DE0403"))
    )
    (comp (ref "L4")
      (value "DLG-0403-180")
      (footprint "eagle-import:DE0403")
      (libsource (lib "eagle-import") (part "EEZ_inductors_and_transformers_DE0403"))
    )
    (comp (ref "LED1")
      (value "LTST-C170YKT")
      (footprint "eagle-import:LED_0805")
      (libsource (lib "eagle-import") (part "LED0805"))
    )
    (comp (ref "OK1")
      (value "TLP291-GB.SE-T")
      (footprint "eagle-import:SO4")
      (libsource (lib "eagle-import") (part "TLP291"))
    )
    (comp (ref "Q1")
      (value "BCP56-16.115")
      (footprint "eagle-import:SOT230P700X180-4N")
      (libsource (lib "eagle-import") (part "BCP56"))
    )
    (comp (ref "R1")
      (value "220K")
      (footprint "eagle-import:R1206")
      (libsource (lib "eagle-import") (part "R-EU_R1206"))
    )
    (comp (ref "R2")
      (value "220K")
      (footprint "eagle-import:R1206")
      (libsource (lib "eagle-import") (part "R-EU_R1206"))
    )
    (comp (ref "R3")
      (value "120R")
      (footprint "eagle-import:R0805")
      (libsource (lib "eagle-import") (part "R-EU_R0805"))
    )
    (comp (ref "R4")
      (value "22R")
      (footprint "eagle-import:R0805")
      (libsource (lib "eagle-import") (part "R-EU_R0805"))
    )
    (comp (ref "R5")
      (value "1K8")
      (footprint "eagle-import:R0805")
      (libsource (lib "eagle-import") (part "R-EU_R0805"))
    )
    (comp (ref "R6")
      (value "120R")
      (footprint "eagle-import:R0805")
      (libsource (lib "eagle-import") (part "R-EU_R0805"))
    )
    (comp (ref "R7")
      (value "220K")
      (footprint "eagle-import:R1206")
      (libsource (lib "eagle-import") (part "R-EU_R1206"))
    )
    (comp (ref "R8")
      (value "220K")
      (footprint "eagle-import:R1206")
      (libsource (lib "eagle-import") (part "R-EU_R1206"))
    )
    (comp (ref "R9")
      (value "100K")
      (footprint "eagle-import:R0805")
      (libsource (lib "eagle-import") (part "R-EU_R0805"))
    )
    (comp (ref "R10")
      (value "120R")
      (footprint "eagle-import:R0805")
      (libsource (lib "eagle-import") (part "R-EU_R0805"))
    )
    (comp (ref "R11")
      (value "120R")
      (footprint "eagle-import:R0805")
      (libsource (lib "eagle-import") (part "R-EU_R0805"))
    )
    (comp (ref "R12")
      (value "16K")
      (footprint "eagle-import:R0805")
      (libsource (lib "eagle-import") (part "R-EU_R0805"))
    )
    (comp (ref "R13")
      (value "470R")
      (footprint "eagle-import:R0805")
      (libsource (lib "eagle-import") (part "R-EU_R0805"))
    )
    (comp (ref "R14")
      (value "5K1")
      (footprint "eagle-import:R0805")
      (libsource (lib "eagle-import") (part "R-EU_R0805"))
    )
    (comp (ref "R15")
      (value "10K")
      (footprint "eagle-import:R0805")
      (libsource (lib "eagle-import") (part "R-EU_R0805"))
    )
    (comp (ref "R16")
      (value "N.C.")
      (footprint "eagle-import:R0805")
      (libsource (lib "eagle-import") (part "R-EU_R0805"))
    )
    (comp (ref "R17")
      (value "47K")
      (footprint "eagle-import:R0805")
      (libsource (lib "eagle-import") (part "R-EU_R0805"))
    )
    (comp (ref "R18")
      (value "750R")
      (footprint "eagle-import:R0805")
      (libsource (lib "eagle-import") (part "R-EU_R0805"))
    )
    (comp (ref "R19")
      (value "12K")
      (footprint "eagle-import:R0805")
      (libsource (lib "eagle-import") (part "R-EU_R0805"))
    )
    (comp (ref "R20")
      (value "1K8")
      (footprint "eagle-import:R0805")
      (libsource (lib "eagle-import") (part "R-EU_R0805"))
    )
    (comp (ref "R21")
      (value "47K")
      (footprint "eagle-import:R0805")
      (libsource (lib "eagle-import") (part "R-EU_R0805"))
    )
    (comp (ref "R22")
      (value "1K")
      (footprint "eagle-import:R0805")
      (libsource (lib "eagle-import") (part "R-EU_R0805"))
    )
    (comp (ref "SAR1")
      (value "PCB 2.4mm")
      (footprint "eagle-import:PCB-SAR_2.4MM")
      (libsource (lib "eagle-import") (part "SARPCB-2.4MM"))
    )
    (comp (ref "SAR2")
      (value "PCB 2.4mm")
      (footprint "eagle-import:PCB-SAR_2.4MM")
      (libsource (lib "eagle-import") (part "SARPCB-2.4MM"))
    )
    (comp (ref "TP1")
      (value "PCB_TEST_TABSHIELD")
      (footprint "eagle-import:PCB_SHIELD_TAB")
      (libsource (lib "eagle-import") (part "PCB_TEST_TABSHIELD"))
    )
    (comp (ref "TP2")
      (value "PCB_TEST_TABSHIELD")
      (footprint "eagle-import:PCB_SHIELD_TAB")
      (libsource (lib "eagle-import") (part "PCB_TEST_TABSHIELD"))
    )
    (comp (ref "TR1")
      (value "Feryster 5572")
      (footprint "eagle-import:FERYSTER_5572")
      (libsource (lib "eagle-import") (part "EEZ_inductors_and_transformers_FERYSTER_5572"))
    )
    (comp (ref "X1")
      (value "B2B-ZR")
      (footprint "eagle-import:B2B-ZR")
      (libsource (lib "eagle-import") (part "B2B-ZR"))
    )
    (comp (ref "X2")
      (value "39-30-1039")
      (footprint "eagle-import:MINIFIT_39301039_CRE")
      (libsource (lib "eagle-import") (part "MINIFIT_39301039-CREEPAGE"))
    )
    (comp (ref "ZD1")
      (value "BZT52C20-DC")
      (footprint "eagle-import:SOD123FL")
      (libsource (lib "eagle-import") (part "ZENER-DIODESOD123FL"))
    )
    (comp (ref "ZD2")
      (value "BZX384-C13")
      (footprint "eagle-import:SOD323-W")
      (libsource (lib "eagle-import") (part "ZENER-DIODESOD323"))
    )
    (comp (ref "ZD3")
      (value "MMSZ5V1T1G")
      (footprint "eagle-import:SOD323-W")
      (libsource (lib "eagle-import") (part "ZENER-DIODESOD323"))
    )
  )
  (nets
    (net (code "1") (name "+2.5VREF") (class "Default")
      (node (ref "C74") (pin "1") (pinfunction "1_1") (pintype "passive"))
      (node (ref "IC9") (pin "3") (pinfunction "+IN1_3") (pintype "input"))
      (node (ref "P1") (pin "E") (pinfunction "E_E") (pintype "passive"))
      (node (ref "R72") (pin "2") (pinfunction "2_2") (pintype "passive"))
      (node (ref "R78") (pin "1") (pinfunction "1_1") (pintype "passive"))
    )
    (net (code "2") (name "+5VREF") (class "Default")
      (node (ref "C48") (pin "2") (pinfunction "2_2") (pintype "passive"))
      (node (ref "C53") (pin "1") (pinfunction "1_1") (pintype "passive"))
      (node (ref "IC5") (pin "4") (pinfunction "REF_4") (pintype "output"))
      (node (ref "NTC1") (pin "1") (pinfunction "P$1_1") (pintype "bidirectional"))
      (node (ref "R36") (pin "1") (pinfunction "1_1") (pintype "passive"))
      (node (ref "R52") (pin "1") (pinfunction "1_1") (pintype "passive"))
      (node (ref "R56") (pin "2") (pinfunction "2_2") (pintype "passive"))
      (node (ref "X4") (pin "1") (pinfunction "1_1") (pintype "passive"))
    )
    (net (code "3") (name "+6V") (class "Default")
      (node (ref "C22") (pin "1") (pinfunction "1_1") (pintype "passive"))
      (node (ref "C25") (pin "1") (pinfunction "1_1") (pintype "passive"))
      (node (ref "D7") (pin "C") (pinfunction "C_C") (pintype "passive"))
      (node (ref "IC2") (pin "8") (pinfunction "IN_8") (pintype "power_in"))
      (node (ref "L4") (pin "2") (pinfunction "2_2") (pintype "passive"))
      (node (ref "R13") (pin "1") (pinfunction "1_1") (pintype "passive"))
      (node (ref "R22") (pin "2") (pinfunction "2_2") (pintype "passive"))
      (node (ref "R65") (pin "1") (pinfunction "1_1") (pintype "passive"))
    )
    (net (code "4") (name "+12V") (class "Default")
      (node (ref "C29") (pin "2") (pinfunction "2_2") (pintype "passive"))
      (node (ref "C30") (pin "2") (pinfunction "2_2") (pintype "passive"))
      (node (ref "C52") (pin "1") (pinfunction "1_1") (pintype "passive"))
      (node (ref "C6") (pin "1") (pinfunction "1_1") (pintype "passive"))
      (node (ref "IC6") (pin "8") (pinfunction "V+_8") (pintype "power_in"))
      (node (ref "OK2") (pin "1") (pinfunction "A_1") (pintype "passive"))
      (node (ref "Q1") (pin "3") (pinfunction "E_3") (pintype "passive"))
      (node (ref "R26") (pin "2") (pinfunction "2_2") (pintype "passive"))
      (node (ref "R37") (pin "2") (pinfunction "2_2") (pintype "passive"))
      (node (ref "R44") (pin "2") (pinfunction "2_2") (pintype "passive"))
      (node (ref "X1") (pin "1") (pinfunction "1_1") (pintype "passive"))
    )
    (net (code "5") (name "0V") (class "Default")
      (node (ref "C13") (pin "-") (pinfunction "-_-") (pintype "passive"))
      (node (ref "C20") (pin "1") (pinfunction "1_1") (pintype "passive"))
      (node (ref "C27") (pin "2") (pinfunction "2_2") (pintype "passive"))
      (node (ref "C28") (pin "2") (pinfunction "2_2") (pintype "passive"))
      (node (ref "C29") (pin "1") (pinfunction "1_1") (pintype "passive"))
      (node (ref "C30") (pin "1") (pinfunction "1_1") (pintype "passive"))
      (node (ref "C31") (pin "-") (pinfunction "-_-") (pintype "passive"))
      (node (ref "C32") (pin "-") (pinfunction "-_-") (pintype "passive"))
      (node (ref "C36") (pin "1") (pinfunction "1_1") (pintype "passive"))
      (node (ref "C38") (pin "2") (pinfunction "2_2") (pintype "passive"))
      (node (ref "C39") (pin "2") (pinfunction "2_2") (pintype "passive"))
      (node (ref "C40") (pin "2") (pinfunction "2_2") (pintype "passive"))
      (node (ref "C43") (pin "2") (pinfunction "2_2") (pintype "passive"))
      (node (ref "C44") (pin "2") (pinfunction "2_2") (pintype "passive"))
      (node (ref "C46") (pin "1") (pinfunction "1_1") (pintype "passive"))
      (node (ref "C47") (pin "1") (pinfunction "1_1") (pintype "passive"))
      (node (ref "C6") (pin "2") (pinfunction "2_2") (pintype "passive"))
      (node (ref "C7") (pin "2") (pinfunction "-_2") (pintype "passive"))
      (node (ref "C8") (pin "2") (pinfunction "2_2") (pintype "passive"))
      (node (ref "D11") (pin "A") (pinfunction "A_A") (pintype "passive"))
      (node (ref "D15") (pin "2") (pinfunction "A_2") (pintype "passive"))
      (node (ref "IC3") (pin "1") (pinfunction "GND_1") (pintype "passive"))
      (node (ref "IC3") (pin "2") (pinfunction "GND_2") (pintype "passive"))
      (node (ref "IC3") (pin "3") (pinfunction "GND_3") (pintype "passive"))
      (node (ref "IC3") (pin "4") (pinfunction "GND_4") (pintype "passive"))
      (node (ref "IC4") (pin "9") (pinfunction "GNDB_9") (pintype "power_in"))
      (node (ref "JP2") (pin "NC") (pinfunction "NC_NC") (pintype "passive"))
      (node (ref "JP3") (pin "1") (pinfunction "1_1") (pintype "passive"))
      (node (ref "OK1") (pin "3") (pinfunction "EMIT_3") (pintype "passive"))
      (node (ref "Q3") (pin "S") (pinfunction "S_S") (pintype "passive"))
      (node (ref "Q4") (pin "S") (pinfunction "S_S") (pintype "passive"))
      (node (ref "Q6") (pin "S") (pinfunction "S_S") (pintype "passive"))
      (node (ref "R19") (pin "1") (pinfunction "1_1") (pintype "passive"))
      (node (ref "R20") (pin "2") (pinfunction "2_2") (pintype "passive"))
      (node (ref "R21") (pin "2") (pinfunction "2_2") (pintype "passive"))
      (node (ref "R38") (pin "2") (pinfunction "2_2") (pintype "passive"))
      (node (ref "R40") (pin "1") (pinfunction "1_1") (pintype "passive"))
      (node (ref "R40") (pin "2") (pinfunction "2_2") (pintype "passive"))
      (node (ref "SH1") (pin "P$2") (pinfunction "GND_B_P$2") (pintype "bidirectional"))
      (node (ref "TP1") (pin "1") (pinfunction "P$1_1") (pintype "bidirectional"))
      (node (ref "TP4") (pin "1") (pinfunction "P$1_1") (pintype "bidirectional"))
      (node (ref "TR1") (pin "6") (pinfunction "S_BIAS_6") (pintype "passive"))
      (node (ref "X1") (pin "2") (pinfunction "1_2") (pintype "passive"))
      (node (ref "ZD1") (pin "A") (pinfunction "A_A") (pintype "passive"))
      (node (ref "ZD2") (pin "A") (pinfunction "A_A") (pintype "passive"))
    )
    (net (code "6") (name "AGND") (class "Default")
      (node (ref "C37") (pin "1") (pinfunction "1_1") (pintype "passive"))
      (node (ref "C42") (pin "2") (pinfunction "2_2") (pintype "passive"))
      (node (ref "C45") (pin "1") (pinfunction "1_1") (pintype "passive"))
      (node (ref "C48") (pin "1") (pinfunction "1_1") (pintype "passive"))
      (node (ref "C49") (pin "1") (pinfunction "1_1") (pintype "passive"))
      (node (ref "C50") (pin "1") (pinfunction "1_1") (pintype "passive"))
      (node (ref "C51") (pin "1") (pinfunction "1_1") (pintype "passive"))
      (node (ref "C52") (pin "2") (pinfunction "2_2") (pintype "passive"))
      (node (ref "C53") (pin "2") (pinfunction "2_2") (pintype "passive"))
      (node (ref "IC4") (pin "4") (pinfunction "GNDI_4") (pintype "power_in"))
      (node (ref "IC4") (pin "5") (pinfunction "DISABLE_5") (pintype "input"))
      (node (ref "IC5") (pin "10") (pinfunction "PGND_10") (pintype "power_in"))
      (node (ref "IC5") (pin "11") (pinfunction "AGND_11") (pintype "power_in"))
      (node (ref "IC5") (pin "2") (pinfunction "FB_2") (pintype "input"))
      (node (ref "IC6") (pin "4") (pinfunction "V-_4") (pintype "power_in"))
      (node (ref "JP3") (pin "2") (pinfunction "2_2") (pintype "passive"))
      (node (ref "OK3") (pin "3") (pinfunction "EMIT_3") (pintype "passive"))
      (node (ref "Q5") (pin "1") (pinfunction "C_1") (pintype "passive"))
      (node (ref "Q7") (pin "C") (pinfunction "C_C") (pintype "passive"))
      (node (ref "R23") (pin "2") (pinfunction "2_2") (pintype "passive"))
      (node (ref "R24") (pin "2") (pinfunction "2_2") (pintype "passive"))
      (node (ref "R25") (pin "2") (pinfunction "2_2") (pintype "passive"))
      (node (ref "R32") (pin "1") (pinfunction "1_1") (pintype "passive"))
      (node (ref "R32") (pin "2") (pinfunction "2_2") (pintype "passive"))
      (node (ref "R33") (pin "1") (pinfunction "1_1") (pintype "passive"))
      (node (ref "R46") (pin "2") (pinfunction "2_2") (pintype "passive"))
      (node (ref "R50") (pin "2") (pinfunction "2_2") (pintype "passive"))
      (node (ref "R51") (pin "2") (pinfunction "2_2") (pintype "passive"))
      (node (ref "R54") (pin "2") (pinfunction "2_2") (pintype "passive"))
      (node (ref "R57") (pin "2") (pinfunction "2_2") (pintype "passive"))
      (node (ref "R58") (pin "2") (pinfunction "2_2") (pintype "passive"))
      (node (ref "R59") (pin "2") (pinfunction "2_2") (pintype "passive"))
      (node (ref "TR2") (pin "1") (pinfunction "S_DOT_1") (pintype "passive"))
      (node (ref "ZD4") (pin "A") (pinfunction "A_A") (pintype "passive"))
      (node (ref "ZD5") (pin "A") (pinfunction "A_A") (pintype "passive"))
    )
    (net (code "7") (name "AUX") (class "Default")
      (node (ref "C3") (pin "2") (pinfunction "2_2") (pintype "passive"))
      (node (ref "D1") (pin "A") (pinfunction "A_A") (pintype "passive"))
      (node (ref "D10") (pin "A") (pinfunction "A_A") (pintype "passive"))
      (node (ref "R16") (pin "2") (pinfunction "2_2") (pintype "passive"))
      (node (ref "TR1") (pin "7") (pinfunction "S_BIAS_DOT_7") (pintype "passive"))
    )
    (net (code "8") (name "AUX_OUT") (class "Default")
      (node (ref "C20") (pin "2") (pinfunction "2_2") (pintype "passive"))
      (node (ref "C7") (pin "1") (pinfunction "+_1") (pintype "passive"))
      (node (ref "IC3") (pin "5") (pinfunction "VDD_5") (pintype "power_in"))
      (node (ref "Q1") (pin "2") (pinfunction "C_2") (pintype "passive"))
      (node (ref "Q1") (pin "4") (pinfunction "C_4") (pintype "passive"))
      (node (ref "R4") (pin "2") (pinfunction "2_2") (pintype "passive"))
      (node (ref "R5") (pin "1") (pinfunction "1_1") (pintype "passive"))
      (node (ref "ZD1") (pin "C") (pinfunction "C_C") (pintype "passive"))
    )
    (net (code "9") (name "BUCK_OUT") (class "Default")
      (node (ref "C33") (pin "2") (pinfunction "2_2") (pintype "passive"))
      (node (ref "C34") (pin "2") (pinfunction "2_2") (pintype "passive"))
      (node (ref "C35") (pin "2") (pinfunction "2_2") (pintype "passive"))
      (node (ref "D15") (pin "1") (pinfunction "C_1") (pintype "passive"))
      (node (ref "IC4") (pin "14") (pinfunction "GNDA_14") (pintype "power_in"))
      (node (ref "L5") (pin "2") (pinfunction "P$2_2") (pintype "bidirectional"))
      (node (ref "L6") (pin "2") (pinfunction "P$2_2") (pintype "bidirectional"))
      (node (ref "Q2") (pin "S") (pinfunction "S_S") (pintype "passive"))
      (node (ref "Q3") (pin "D") (pinfunction "D_D") (pintype "passive"))
      (node (ref "TP3") (pin "1") (pinfunction "P$1_1") (pintype "bidirectional"))
    )
    (net (code "10") (name "CT_OUT") (class "Default")
      (node (ref "D12") (pin "C") (pinfunction "C_C") (pintype "passive"))
      (node (ref "R24") (pin "1") (pinfunction "1_1") (pintype "passive"))
      (node (ref "R25") (pin "1") (pinfunction "1_1") (pintype "passive"))
      (node (ref "R53") (pin "1") (pinfunction "1_1") (pintype "passive"))
    )
    (net (code "11") (name "DC_BUS") (class "Default")
      (node (ref "B1") (pin "+") (pinfunction "+_+") (pintype "passive"))
      (node (ref "C12") (pin "1") (pinfunction "1_1") (pintype "passive"))
      (node (ref "C13") (pin "+") (pinfunction "+_+") (pintype "passive"))
      (node (ref "C31") (pin "+") (pinfunction "+_+") (pintype "passive"))
      (node (ref "C32") (pin "+") (pinfunction "+_+") (pintype "passive"))
      (node (ref "C36") (pin "2") (pinfunction "2_2") (pintype "passive"))
      (node (ref "R35") (pin "1") (pinfunction "1_1") (pintype "passive"))
      (node (ref "R41") (pin "2") (pinfunction "2_2") (pintype "passive"))
      (node (ref "R42") (pin "2") (pinfunction "2_2") (pintype "passive"))
      (node (ref "R7") (pin "1") (pinfunction "1_1") (pintype "passive"))
      (node (ref "R8") (pin "1") (pinfunction "1_1") (pintype "passive"))
      (node (ref "TR1") (pin "1") (pinfunction "SHIELD_1") (pintype "passive"))
      (node (ref "TR1") (pin "2") (pinfunction "P_2") (pintype "passive"))
      (node (ref "TR2") (pin "7") (pinfunction "P_7") (pintype "passive"))
    )
    (net (code "12") (name "DC_OUT") (class "Default")
      (node (ref "C11") (pin "1") (pinfunction "1_1") (pintype "passive"))
      (node (ref "L2") (pin "2") (pinfunction "2_2") (pintype "passive"))
      (node (ref "X3") (pin "3") (pinfunction "S_3") (pintype "passive"))
    )
    (net (code "13") (name "GND") (class "Default")
      (node (ref "C14") (pin "1") (pinfunction "+_1") (pintype "passive"))
      (node (ref "C15") (pin "1") (pinfunction "1_1") (pintype "passive"))
      (node (ref "C16") (pin "1") (pinfunction "1_1") (pintype "passive"))
      (node (ref "C17") (pin "1") (pinfunction "1_1") (pintype "passive"))
      (node (ref "C19") (pin "2") (pinfunction "2_2") (pintype "passive"))
      (node (ref "C22") (pin "2") (pinfunction "2_2") (pintype "passive"))
      (node (ref "C23") (pin "-") (pinfunction "-_-") (pintype "passive"))
      (node (ref "C24") (pin "-") (pinfunction "-_-") (pintype "passive"))
      (node (ref "C25") (pin "2") (pinfunction "2_2") (pintype "passive"))
      (node (ref "C54") (pin "-") (pinfunction "-_-") (pintype "passive"))
      (node (ref "C55") (pin "-") (pinfunction "-_-") (pintype "passive"))
      (node (ref "C56") (pin "-") (pinfunction "-_-") (pintype "passive"))
      (node (ref "C57") (pin "2") (pinfunction "2_2") (pintype "passive"))
      (node (ref "C58") (pin "2") (pinfunction "2_2") (pintype "passive"))
      (node (ref "C59") (pin "2") (pinfunction "2_2") (pintype "passive"))
      (node (ref "C60") (pin "2") (pinfunction "2_2") (pintype "passive"))
      (node (ref "C61") (pin "2") (pinfunction "2_2") (pintype "passive"))
      (node (ref "C62") (pin "1") (pinfunction "1_1") (pintype "passive"))
      (node (ref "C63") (pin "2") (pinfunction "2_2") (pintype "passive"))
      (node (ref "C64") (pin "2") (pinfunction "2_2") (pintype "passive"))
      (node (ref "C65") (pin "2") (pinfunction "2_2") (pintype "passive"))
      (node (ref "C66") (pin "2") (pinfunction "2_2") (pintype "passive"))
      (node (ref "C67") (pin "2") (pinfunction "2_2") (pintype "passive"))
      (node (ref "C68") (pin "2") (pinfunction "2_2") (pintype "passive"))
      (node (ref "C69") (pin "2") (pinfunction "2_2") (pintype "passive"))
      (node (ref "C73") (pin "-") (pinfunction "-_-") (pintype "passive"))
      (node (ref "C74") (pin "2") (pinfunction "2_2") (pintype "passive"))
      (node (ref "D3") (pin "C") (pinfunction "C_C") (pintype "passive"))
      (node (ref "D9") (pin "A") (pinfunction "A_A") (pintype "passive"))
      (node (ref "IC1") (pin "5") (pinfunction "GND_5") (pintype "passive"))
      (node (ref "IC10") (pin "3") (pinfunction "A_3") (pintype "passive"))
      (node (ref "IC2") (pin "4") (pinfunction "GND_4") (pintype "passive"))
      (node (ref "IC7") (pin "6") (pinfunction "VS_6") (pintype "passive"))
      (node (ref "IC7") (pin "7") (pinfunction "GND_7") (pintype "power_in"))
      (node (ref "IC8") (pin "3") (pinfunction "+IN_3") (pintype "input"))
      (node (ref "IC8") (pin "5") (pinfunction "+IN_5") (pintype "input"))
      (node (ref "IC9") (pin "4") (pinfunction "VCC-_4") (pintype "power_in"))
      (node (ref "JP1") (pin "NO") (pinfunction "NO_NO") (pintype "passive"))
      (node (ref "LED1") (pin "C") (pinfunction "C_C") (pintype "passive"))
      (node (ref "OK2") (pin "3") (pinfunction "EMIT_3") (pintype "passive"))
      (node (ref "P1") (pin "A") (pinfunction "A_A") (pintype "passive"))
      (node (ref "Q8") (pin "2") (pinfunction "S_2") (pintype "passive"))
      (node (ref "Q9") (pin "2") (pinfunction "S_2") (pintype "passive"))
      (node (ref "R14") (pin "2") (pinfunction "2_2") (pintype "passive"))
      (node (ref "R66") (pin "2") (pinfunction "2_2") (pintype "passive"))
      (node (ref "R86") (pin "1") (pinfunction "1_1") (pintype "passive"))
      (node (ref "TP2") (pin "1") (pinfunction "P$1_1") (pintype "bidirectional"))
      (node (ref "TP7") (pin "GND") (pinfunction "GND_GND") (pintype "bidirectional"))
      (node (ref "TR1") (pin "10") (pinfunction "S1_10") (pintype "passive"))
      (node (ref "TR1") (pin "11") (pinfunction "S1_11") (pintype "passive"))
      (node (ref "TR1") (pin "9") (pinfunction "S2_DOT_9") (pintype "passive"))
      (node (ref "X3") (pin "6") (pinfunction "S_6") (pintype "passive"))
      (node (ref "X5") (pin "2") (pinfunction "1_2") (pintype "passive"))
      (node (ref "ZD3") (pin "A") (pinfunction "A_A") (pintype "passive"))
      (node (ref "ZD6") (pin "A") (pinfunction "A_A") (pintype "passive"))
    )
    (net (code "14") (name "GNDA") (class "Default")
      (node (ref "B1") (pin "-") (pinfunction "-_-") (pintype "passive"))
      (node (ref "SH1") (pin "P$1") (pinfunction "GND_A_P$1") (pintype "bidirectional"))
    )
    (net (code "15") (name "HD") (class "Default")
      (node (ref "IC5") (pin "5") (pinfunction "HD_5") (pintype "output"))
      (node (ref "R28") (pin "2") (pinfunction "2_2") (pintype "passive"))
    )
    (net (code "16") (name "HI_OUT") (class "Default")
      (node (ref "D14") (pin "A") (pinfunction "A_A") (pintype "passive"))
      (node (ref "IC4") (pin "15") (pinfunction "VOA_15") (pintype "output"))
      (node (ref "R27") (pin "2") (pinfunction "2_2") (pintype "passive"))
    )
    (net (code "17") (name "ISO_FB") (class "Default")
      (node (ref "C50") (pin "2") (pinfunction "2_2") (pintype "passive"))
      (node (ref "IC5") (pin "3") (pinfunction "COMP_3") (pintype "passive"))
      (node (ref "OK3") (pin "4") (pinfunction "COL_4") (pintype "passive"))
      (node (ref "Q7") (pin "E") (pinfunction "E_E") (pintype "passive"))
      (node (ref "R55") (pin "1") (pinfunction "1_1") (pintype "passive"))
      (node (ref "TP6") (pin "1") (pinfunction "P$1_1") (pintype "bidirectional"))
    )
    (net (code "18") (name "LD") (class "Default")
      (node (ref "IC5") (pin "6") (pinfunction "LD_6") (pintype "output"))
      (node (ref "R30") (pin "2") (pinfunction "2_2") (pintype "passive"))
    )
    (net (code "19") (name "LO_OUT") (class "Default")
      (node (ref "D17") (pin "A") (pinfunction "A_A") (pintype "passive"))
      (node (ref "IC4") (pin "10") (pinfunction "VOB_10") (pintype "output"))
      (node (ref "R34") (pin "1") (pinfunction "1_1") (pintype "passive"))
    )
    (net (code "20") (name "Net-(C3-Pad1)") (class "Default")
      (node (ref "C3") (pin "1") (pinfunction "1_1") (pintype "passive"))
      (node (ref "R3") (pin "2") (pinfunction "2_2") (pintype "passive"))
    )
    (net (code "21") (name "Net-(C9-Pad1)") (class "Default")
      (node (ref "C9") (pin "1") (pinfunction "1_1") (pintype "passive"))
      (node (ref "R6") (pin "2") (pinfunction "2_2") (pintype "passive"))
    )
    (net (code "22") (name "Net-(C10-+)") (class "Default")
      (node (ref "C10") (pin "1") (pinfunction "+_1") (pintype "passive"))
      (node (ref "D2") (pin "C") (pinfunction "C_C") (pintype "passive"))
      (node (ref "L2") (pin "1") (pinfunction "1_1") (pintype "passive"))
      (node (ref "R6") (pin "1") (pinfunction "1_1") (pintype "passive"))
    )
    (net (code "23") (name "Net-(C10--)") (class "Default")
      (node (ref "C10") (pin "2") (pinfunction "-_2") (pintype "passive"))
      (node (ref "C11") (pin "2") (pinfunction "2_2") (pintype "passive"))
      (node (ref "JP1") (pin "COM") (pinfunction "COM_COM") (pintype "passive"))
      (node (ref "TR1") (pin "14") (pinfunction "S3_14") (pintype "passive"))
    )
    (net (code "24") (name "Net-(C12-Pad2)") (class "Default")
      (node (ref "C12") (pin "2") (pinfunction "2_2") (pintype "passive"))
      (node (ref "D4") (pin "C") (pinfunction "C_C") (pintype "passive"))
      (node (ref "R7") (pin "2") (pinfunction "2_2") (pintype "passive"))
    )
    (net (code "25") (name "Net-(C14--)") (class "Default")
      (node (ref "C14") (pin "2") (pinfunction "-_2") (pintype "passive"))
      (node (ref "D5") (pin "A") (pinfunction "A_A") (pintype "passive"))
      (node (ref "L3") (pin "1") (pinfunction "1_1") (pintype "passive"))
      (node (ref "R10") (pin "1") (pinfunction "1_1") (pintype "passive"))
    )
    (net (code "26") (name "Net-(C18-Pad1)") (class "Default")
      (node (ref "C18") (pin "1") (pinfunction "1_1") (pintype "passive"))
      (node (ref "R10") (pin "2") (pinfunction "2_2") (pintype "passive"))
    )
    (net (code "27") (name "Net-(C19-Pad1)") (class "Default")
      (node (ref "C19") (pin "1") (pinfunction "1_1") (pintype "passive"))
      (node (ref "JP2") (pin "COM") (pinfunction "COM_COM") (pintype "passive"))
    )
    (net (code "28") (name "Net-(C21-Pad1)") (class "Default")
      (node (ref "C21") (pin "1") (pinfunction "1_1") (pintype "passive"))
      (node (ref "R11") (pin "2") (pinfunction "2_2") (pintype "passive"))
    )
    (net (code "29") (name "Net-(C21-Pad2)") (class "Default")
      (node (ref "C21") (pin "2") (pinfunction "2_2") (pintype "passive"))
      (node (ref "D8") (pin "A") (pinfunction "A_A") (pintype "passive"))
      (node (ref "TR1") (pin "12") (pinfunction "S1_DOT_12") (pintype "passive"))
      (node (ref "TR1") (pin "13") (pinfunction "S1_DOT_13") (pintype "passive"))
    )
    (net (code "30") (name "Net-(C24-Pad+)") (class "Default")
      (node (ref "C24") (pin "+") (pinfunction "+_+") (pintype "passive"))
      (node (ref "D8") (pin "C") (pinfunction "C_C") (pintype "passive"))
      (node (ref "L4") (pin "1") (pinfunction "1_1") (pintype "passive"))
      (node (ref "R11") (pin "1") (pinfunction "1_1") (pintype "passive"))
      (node (ref "R18") (pin "1") (pinfunction "1_1") (pintype "passive"))
    )
    (net (code "31") (name "Net-(C26-Pad1)") (class "Default")
      (node (ref "C26") (pin "1") (pinfunction "1_1") (pintype "passive"))
      (node (ref "R21") (pin "1") (pinfunction "1_1") (pintype "passive"))
    )
    (net (code "32") (name "Net-(C41-Pad1)") (class "Default")
      (node (ref "C41") (pin "1") (pinfunction "1_1") (pintype "passive"))
      (node (ref "R31") (pin "1") (pinfunction "1_1") (pintype "passive"))
    )
    (net (code "33") (name "Net-(C46-Pad2)") (class "Default")
      (node (ref "C46") (pin "2") (pinfunction "2_2") (pintype "passive"))
      (node (ref "C47") (pin "2") (pinfunction "2_2") (pintype "passive"))
      (node (ref "D18") (pin "1") (pinfunction "C_1") (pintype "passive"))
      (node (ref "D18") (pin "3") (pinfunction "C_3") (pintype "passive"))
      (node (ref "D19") (pin "1") (pinfunction "C_1") (pintype "passive"))
      (node (ref "D19") (pin "3") (pinfunction "C_3") (pintype "passive"))
      (node (ref "R41") (pin "1") (pinfunction "1_1") (pintype "passive"))
      (node (ref "R42") (pin "1") (pinfunction "1_1") (pintype "passive"))
    )
    (net (code "34") (name "Net-(C51-Pad2)") (class "Default")
      (node (ref "C51") (pin "2") (pinfunction "2_2") (pintype "passive"))
      (node (ref "R55") (pin "2") (pinfunction "2_2") (pintype "passive"))
    )
    (net (code "35") (name "Net-(C62-Pad2)") (class "Default")
      (node (ref "C62") (pin "2") (pinfunction "2_2") (pintype "passive"))
      (node (ref "R61") (pin "1") (pinfunction "1_1") (pintype "passive"))
    )
    (net (code "36") (name "Net-(C63-Pad1)") (class "Default")
      (node (ref "C63") (pin "1") (pinfunction "1_1") (pintype "passive"))
      (node (ref "R62") (pin "2") (pinfunction "2_2") (pintype "passive"))
      (node (ref "R63") (pin "2") (pinfunction "2_2") (pintype "passive"))
    )
    (net (code "37") (name "Net-(C67-Pad1)") (class "Default")
      (node (ref "C67") (pin "1") (pinfunction "1_1") (pintype "passive"))
      (node (ref "R68") (pin "2") (pinfunction "2_2") (pintype "passive"))
      (node (ref "R69") (pin "2") (pinfunction "2_2") (pintype "passive"))
    )
    (net (code "38") (name "Net-(C72-Pad2)") (class "Default")
      (node (ref "C72") (pin "2") (pinfunction "2_2") (pintype "passive"))
      (node (ref "R80") (pin "2") (pinfunction "2_2") (pintype "passive"))
    )
    (net (code "39") (name "Net-(C73-Pad+)") (class "Default")
      (node (ref "C73") (pin "+") (pinfunction "+_+") (pintype "passive"))
      (node (ref "R73") (pin "1") (pinfunction "1_1") (pintype "passive"))
      (node (ref "R82") (pin "1") (pinfunction "1_1") (pintype "passive"))
      (node (ref "R83") (pin "1") (pinfunction "1_1") (pintype "passive"))
    )
    (net (code "40") (name "Net-(C76-Pad2)") (class "Default")
      (node (ref "C76") (pin "2") (pinfunction "2_2") (pintype "passive"))
      (node (ref "R85") (pin "1") (pinfunction "1_1") (pintype "passive"))
    )
    (net (code "41") (name "Net-(D1-PadC)") (class "Default")
      (node (ref "D1") (pin "C") (pinfunction "C_C") (pintype "passive"))
      (node (ref "R3") (pin "1") (pinfunction "1_1") (pintype "passive"))
      (node (ref "R4") (pin "1") (pinfunction "1_1") (pintype "passive"))
    )
    (net (code "42") (name "Net-(D10-PadC)") (class "Default")
      (node (ref "D10") (pin "C") (pinfunction "C_C") (pintype "passive"))
      (node (ref "D11") (pin "C") (pinfunction "C_C") (pintype "passive"))
      (node (ref "R17") (pin "2") (pinfunction "2_2") (pintype "passive"))
    )
    (net (code "43") (name "Net-(D13-A)") (class "Default")
      (node (ref "D13") (pin "2") (pinfunction "A_2") (pintype "passive"))
      (node (ref "R26") (pin "1") (pinfunction "1_1") (pintype "passive"))
    )
    (net (code "44") (name "Net-(D14-PadC)") (class "Default")
      (node (ref "D14") (pin "C") (pinfunction "C_C") (pintype "passive"))
      (node (ref "Q2") (pin "G") (pinfunction "G_G") (pintype "passive"))
      (node (ref "R27") (pin "1") (pinfunction "1_1") (pintype "passive"))
    )
    (net (code "45") (name "Net-(D16-PadA)") (class "Default")
      (node (ref "D16") (pin "A") (pinfunction "A_A") (pintype "passive"))
      (node (ref "R37") (pin "1") (pinfunction "1_1") (pintype "passive"))
    )
    (net (code "46") (name "Net-(D17-PadC)") (class "Default")
      (node (ref "D17") (pin "C") (pinfunction "C_C") (pintype "passive"))
      (node (ref "Q3") (pin "G") (pinfunction "G_G") (pintype "passive"))
      (node (ref "R34") (pin "2") (pinfunction "2_2") (pintype "passive"))
      (node (ref "R38") (pin "1") (pinfunction "1_1") (pintype "passive"))
    )
    (net (code "47") (name "Net-(D18-A)") (class "Default")
      (node (ref "C41") (pin "2") (pinfunction "2_2") (pintype "passive"))
      (node (ref "D18") (pin "2") (pinfunction "A_2") (pintype "passive"))
      (node (ref "L6") (pin "1") (pinfunction "P$1_1") (pintype "bidirectional"))
      (node (ref "Q6") (pin "D") (pinfunction "D_D") (pintype "passive"))
      (node (ref "TR3") (pin "P1_DOT") (pinfunction "P_DOT_P1_DOT") (pintype "passive"))
    )
    (net (code "48") (name "Net-(D19-A)") (class "Default")
      (node (ref "D19") (pin "2") (pinfunction "A_2") (pintype "passive"))
      (node (ref "L5") (pin "1") (pinfunction "P$1_1") (pintype "bidirectional"))
      (node (ref "Q4") (pin "D") (pinfunction "D_D") (pintype "passive"))
      (node (ref "R29") (pin "2") (pinfunction "2_2") (pintype "passive"))
      (node (ref "TR3") (pin "P1") (pinfunction "P_P1") (pintype "passive"))
    )
    (net (code "49") (name "Net-(D20-PadA)") (class "Default")
      (node (ref "D20") (pin "A") (pinfunction "A_A") (pintype "passive"))
      (node (ref "LED2") (pin "C") (pinfunction "C_C") (pintype "passive"))
    )
    (net (code "50") (name "Net-(D22-PadC)") (class "Default")
      (node (ref "D22") (pin "C") (pinfunction "C_C") (pintype "passive"))
      (node (ref "Q4") (pin "G") (pinfunction "G_G") (pintype "passive"))
      (node (ref "R47") (pin "1") (pinfunction "1_1") (pintype "passive"))
    )
    (net (code "51") (name "Net-(D23-PadC)") (class "Default")
      (node (ref "D23") (pin "C") (pinfunction "C_C") (pintype "passive"))
      (node (ref "Q6") (pin "G") (pinfunction "G_G") (pintype "passive"))
      (node (ref "R48") (pin "1") (pinfunction "1_1") (pintype "passive"))
    )
    (net (code "52") (name "Net-(IC2-FB)") (class "Default")
      (node (ref "IC2") (pin "7") (pinfunction "FB_7") (pintype "input"))
      (node (ref "R12") (pin "2") (pinfunction "2_2") (pintype "passive"))
      (node (ref "R14") (pin "1") (pinfunction "1_1") (pintype "passive"))
    )
    (net (code "53") (name "Net-(IC3-BR)") (class "Default")
      (node (ref "IC3") (pin "8") (pinfunction "BR_8") (pintype "input"))
      (node (ref "R20") (pin "1") (pinfunction "1_1") (pintype "passive"))
      (node (ref "R9") (pin "2") (pinfunction "2_2") (pintype "passive"))
    )
    (net (code "54") (name "Net-(IC3-FB)") (class "Default")
      (node (ref "C26") (pin "2") (pinfunction "2_2") (pintype "passive"))
      (node (ref "C28") (pin "1") (pinfunction "1_1") (pintype "passive"))
      (node (ref "IC3") (pin "7") (pinfunction "FB_7") (pintype "input"))
      (node (ref "OK1") (pin "4") (pinfunction "COL_4") (pintype "passive"))
    )
    (net (code "55") (name "Net-(IC3-ZCD)") (class "Default")
      (node (ref "C27") (pin "1") (pinfunction "1_1") (pintype "passive"))
      (node (ref "IC3") (pin "6") (pinfunction "ZCD_6") (pintype "input"))
      (node (ref "R16") (pin "1") (pinfunction "1_1") (pintype "passive"))
      (node (ref "R17") (pin "1") (pinfunction "1_1") (pintype "passive"))
      (node (ref "R19") (pin "2") (pinfunction "2_2") (pintype "passive"))
    )
    (net (code "56") (name "Net-(IC4-DT)") (class "Default")
      (node (ref "IC4") (pin "6") (pinfunction "DT_6") (pintype "input"))
      (node (ref "R33") (pin "2") (pinfunction "2_2") (pintype "passive"))
    )
    (net (code "57") (name "Net-(IC4-VDDA)") (class "Default")
      (node (ref "C33") (pin "1") (pinfunction "1_1") (pintype "passive"))
      (node (ref "C34") (pin "1") (pinfunction "1_1") (pintype "passive"))
      (node (ref "C35") (pin "1") (pinfunction "1_1") (pintype "passive"))
      (node (ref "D13") (pin "1") (pinfunction "C_1") (pintype "passive"))
      (node (ref "D13") (pin "3") (pinfunction "C_3") (pintype "passive"))
      (node (ref "IC4") (pin "16") (pinfunction "VDDA_16") (pintype "power_in"))
    )
    (net (code "58") (name "Net-(IC4-VDDB)") (class "Default")
      (node (ref "C38") (pin "1") (pinfunction "1_1") (pintype "passive"))
      (node (ref "C39") (pin "1") (pinfunction "1_1") (pintype "passive"))
      (node (ref "C40") (pin "1") (pinfunction "1_1") (pintype "passive"))
      (node (ref "D16") (pin "C") (pinfunction "C_C") (pintype "passive"))
      (node (ref "IC4") (pin "11") (pinfunction "VDDB_11") (pintype "power_in"))
    )
    (net (code "59") (name "Net-(IC4-VIA)") (class "Default")
      (node (ref "IC4") (pin "1") (pinfunction "VIA_1") (pintype "input"))
      (node (ref "R28") (pin "1") (pinfunction "1_1") (pintype "passive"))
    )
    (net (code "60") (name "Net-(IC4-VIB)") (class "Default")
      (node (ref "IC4") (pin "2") (pinfunction "VIB_2") (pintype "input"))
      (node (ref "R30") (pin "1") (pinfunction "1_1") (pintype "passive"))
    )
    (net (code "61") (name "Net-(IC5-CS)") (class "Default")
      (node (ref "C49") (pin "2") (pinfunction "2_2") (pintype "passive"))
      (node (ref "IC5") (pin "12") (pinfunction "CS_12") (pintype "input"))
      (node (ref "R53") (pin "2") (pinfunction "2_2") (pintype "passive"))
    )
    (net (code "62") (name "Net-(IC5-RT{slash}SYNC)") (class "Default")
      (node (ref "IC5") (pin "15") (pinfunction "RT/SYNC_15") (pintype "input"))
      (node (ref "R51") (pin "1") (pinfunction "1_1") (pintype "passive"))
    )
    (net (code "63") (name "Net-(IC5-SS)") (class "Default")
      (node (ref "C45") (pin "2") (pinfunction "2_2") (pintype "passive"))
      (node (ref "IC5") (pin "13") (pinfunction "SS_13") (pintype "passive"))
    )
    (net (code "64") (name "Net-(IC5-TIME)") (class "Default")
      (node (ref "IC5") (pin "14") (pinfunction "TIME_14") (pintype "input"))
      (node (ref "R50") (pin "1") (pinfunction "1_1") (pintype "passive"))
    )
    (net (code "65") (name "Net-(IC5-UVLO)") (class "Default")
      (node (ref "IC5") (pin "16") (pinfunction "UVLO_16") (pintype "input"))
      (node (ref "R45") (pin "1") (pinfunction "1_1") (pintype "passive"))
      (node (ref "ZD5") (pin "C") (pinfunction "C_C") (pintype "passive"))
    )
    (net (code "66") (name "Net-(IC5-VCC)") (class "Default")
      (node (ref "C43") (pin "1") (pinfunction "1_1") (pintype "passive"))
      (node (ref "C44") (pin "1") (pinfunction "1_1") (pintype "passive"))
      (node (ref "IC5") (pin "1") (pinfunction "VIN_1") (pintype "input"))
      (node (ref "IC5") (pin "7") (pinfunction "VCC_7") (pintype "power_in"))
      (node (ref "R44") (pin "1") (pinfunction "1_1") (pintype "passive"))
    )
    (net (code "67") (name "Net-(IC6A-+IN)") (class "Default")
      (node (ref "IC6") (pin "3") (pinfunction "+IN_3") (pintype "input"))
      (node (ref "NTC1") (pin "2") (pinfunction "P$2_2") (pintype "bidirectional"))
      (node (ref "R59") (pin "1") (pinfunction "1_1") (pintype "passive"))
      (node (ref "X4") (pin "2") (pinfunction "1_2") (pintype "passive"))
    )
    (net (code "68") (name "Net-(IC6A--IN)") (class "Default")
      (node (ref "IC6") (pin "1") (pinfunction "OUT_1") (pintype "output"))
      (node (ref "IC6") (pin "2") (pinfunction "-IN_2") (pintype "input"))
      (node (ref "IC6") (pin "5") (pinfunction "+IN_5") (pintype "input"))
    )
    (net (code "69") (name "Net-(IC6B--IN)") (class "Default")
      (node (ref "IC6") (pin "6") (pinfunction "-IN_6") (pintype "input"))
      (node (ref "R56") (pin "1") (pinfunction "1_1") (pintype "passive"))
      (node (ref "R58") (pin "1") (pinfunction "1_1") (pintype "passive"))
    )
    (net (code "70") (name "Net-(IC6B-OUT)") (class "Default")
      (node (ref "IC6") (pin "7") (pinfunction "OUT_7") (pintype "output"))
      (node (ref "R49") (pin "2") (pinfunction "2_2") (pintype "passive"))
      (node (ref "R57") (pin "1") (pinfunction "1_1") (pintype "passive"))
    )
    (net (code "71") (name "Net-(IC7-GATE1)") (class "Default")
      (node (ref "D24") (pin "C") (pinfunction "C_C") (pintype "passive"))
      (node (ref "IC7") (pin "1") (pinfunction "GATE1_1") (pintype "output"))
      (node (ref "R64") (pin "2") (pinfunction "2_2") (pintype "passive"))
    )
    (net (code "72") (name "Net-(IC7-GATE2)") (class "Default")
      (node (ref "D25") (pin "C") (pinfunction "C_C") (pintype "passive"))
      (node (ref "IC7") (pin "8") (pinfunction "GATE2_8") (pintype "output"))
      (node (ref "R67") (pin "2") (pinfunction "2_2") (pintype "passive"))
    )
    (net (code "73") (name "Net-(IC7-MOT)") (class "Default")
      (node (ref "IC7") (pin "3") (pinfunction "MOT_3") (pintype "passive"))
      (node (ref "R66") (pin "1") (pinfunction "1_1") (pintype "passive"))
    )
    (net (code "74") (name "Net-(IC7-VCC)") (class "Default")
      (node (ref "C64") (pin "1") (pinfunction "1_1") (pintype "passive"))
      (node (ref "C65") (pin "1") (pinfunction "1_1") (pintype "passive"))
      (node (ref "IC7") (pin "2") (pinfunction "VCC_2") (pintype "power_in"))
      (node (ref "R65") (pin "2") (pinfunction "2_2") (pintype "passive"))
    )
    (net (code "75") (name "Net-(IC8A--IN)") (class "Default")
      (node (ref "C70") (pin "2") (pinfunction "2_2") (pintype "passive"))
      (node (ref "IC8") (pin "2") (pinfunction "-IN_2") (pintype "input"))
      (node (ref "R74") (pin "2") (pinfunction "2_2") (pintype "passive"))
      (node (ref "R75") (pin "1") (pinfunction "1_1") (pintype "passive"))
      (node (ref "R79") (pin "1") (pinfunction "1_1") (pintype "passive"))
    )
    (net (code "76") (name "Net-(IC8A-OUT)") (class "Default")
      (node (ref "C70") (pin "1") (pinfunction "1_1") (pintype "passive"))
      (node (ref "IC8") (pin "1") (pinfunction "OUT_1") (pintype "output"))
      (node (ref "R83") (pin "2") (pinfunction "2_2") (pintype "passive"))
    )
    (net (code "77") (name "Net-(IC8B--IN)") (class "Default")
      (node (ref "IC8") (pin "6") (pinfunction "-IN_6") (pintype "input"))
      (node (ref "R70") (pin "2") (pinfunction "2_2") (pintype "passive"))
      (node (ref "R72") (pin "1") (pinfunction "1_1") (pintype "passive"))
    )
    (net (code "78") (name "Net-(IC8B-OUT)") (class "Default")
      (node (ref "IC8") (pin "7") (pinfunction "OUT_7") (pintype "output"))
      (node (ref "R70") (pin "1") (pinfunction "1_1") (pintype "passive"))
      (node (ref "R75") (pin "2") (pinfunction "2_2") (pintype "passive"))
    )
    (net (code "79") (name "Net-(IC9A--IN1)") (class "Default")
      (node (ref "C71") (pin "2") (pinfunction "2_2") (pintype "passive"))
      (node (ref "IC9") (pin "2") (pinfunction "-IN1_2") (pintype "input"))
      (node (ref "R80") (pin "1") (pinfunction "1_1") (pintype "passive"))
      (node (ref "R81") (pin "1") (pinfunction "1_1") (pintype "passive"))
    )
    (net (code "80") (name "Net-(IC9B-+IN)") (class "Default")
      (node (ref "IC9") (pin "5") (pinfunction "+IN_5") (pintype "input"))
      (node (ref "JP4") (pin "COM") (pinfunction "COM_COM") (pintype "passive"))
    )
    (net (code "81") (name "Net-(IC9B--IN)") (class "Default")
      (node (ref "IC9") (pin "6") (pinfunction "-IN_6") (pintype "input"))
      (node (ref "IC9") (pin "7") (pinfunction "OUT_7") (pintype "output"))
      (node (ref "R79") (pin "2") (pinfunction "2_2") (pintype "passive"))
    )
    (net (code "82") (name "Net-(IC10-C)") (class "Default")
      (node (ref "C71") (pin "1") (pinfunction "1_1") (pintype "passive"))
      (node (ref "C72") (pin "1") (pinfunction "1_1") (pintype "passive"))
      (node (ref "C75") (pin "1") (pinfunction "1_1") (pintype "passive"))
      (node (ref "C76") (pin "1") (pinfunction "1_1") (pintype "passive"))
      (node (ref "IC10") (pin "1") (pinfunction "C_1") (pintype "passive"))
      (node (ref "IC9") (pin "1") (pinfunction "OUT1_1") (pintype "output"))
      (node (ref "OK3") (pin "2") (pinfunction "C_2") (pintype "passive"))
      (node (ref "R84") (pin "2") (pinfunction "2_2") (pintype "passive"))
    )
    (net (code "83") (name "Net-(IC10-REF)") (class "Default")
      (node (ref "C75") (pin "2") (pinfunction "2_2") (pintype "passive"))
      (node (ref "IC10") (pin "2") (pinfunction "REF_2") (pintype "passive"))
      (node (ref "R77") (pin "1") (pinfunction "1_1") (pintype "passive"))
      (node (ref "R81") (pin "2") (pinfunction "2_2") (pintype "passive"))
      (node (ref "R82") (pin "2") (pinfunction "2_2") (pintype "passive"))
      (node (ref "R85") (pin "2") (pinfunction "2_2") (pintype "passive"))
      (node (ref "R86") (pin "2") (pinfunction "2_2") (pintype "passive"))
      (node (ref "TP8") (pin "1") (pinfunction "P$1_1") (pintype "bidirectional"))
    )
    (net (code "84") (name "Net-(JP4-PadNO)") (class "Default")
      (node (ref "JP4") (pin "NO") (pinfunction "NO_NO") (pintype "passive"))
      (node (ref "P1") (pin "S") (pinfunction "S_S") (pintype "passive"))
    )
    (net (code "85") (name "Net-(L1B-1)") (class "Default")
      (node (ref "B1") (pin "AC2") (pinfunction "AC2_AC2") (pintype "passive"))
      (node (ref "C2") (pin "2") (pinfunction "2_2") (pintype "passive"))
      (node (ref "C4") (pin "2") (pinfunction "2_2") (pintype "passive"))
      (node (ref "L1") (pin "3") (pinfunction "1_3") (pintype "passive"))
      (node (ref "SAR2") (pin "2") (pinfunction "P$2_2") (pintype "bidirectional"))
    )
    (net (code "86") (name "Net-(L1B-2)") (class "Default")
      (node (ref "C1") (pin "2") (pinfunction "2_2") (pintype "passive"))
      (node (ref "C4A") (pin "2") (pinfunction "2_2") (pintype "passive"))
      (node (ref "L1") (pin "4") (pinfunction "2_4") (pintype "passive"))
      (node (ref "R2") (pin "2") (pinfunction "2_2") (pintype "passive"))
      (node (ref "SAR2") (pin "1") (pinfunction "P$1_1") (pintype "bidirectional"))
      (node (ref "X2") (pin "3") (pinfunction "1_3") (pintype "passive"))
    )
    (net (code "87") (name "Net-(LED1-PadA)") (class "Default")
      (node (ref "LED1") (pin "A") (pinfunction "A_A") (pintype "passive"))
      (node (ref "R13") (pin "2") (pinfunction "2_2") (pintype "passive"))
    )
    (net (code "88") (name "Net-(LED2-PadA)") (class "Default")
      (node (ref "LED2") (pin "A") (pinfunction "A_A") (pintype "passive"))
      (node (ref "R39") (pin "2") (pinfunction "2_2") (pintype "passive"))
    )
    (net (code "89") (name "Net-(OK1-A)") (class "Default")
      (node (ref "OK1") (pin "1") (pinfunction "A_1") (pintype "passive"))
      (node (ref "R18") (pin "2") (pinfunction "2_2") (pintype "passive"))
    )
    (net (code "90") (name "Net-(OK1-C)") (class "Default")
      (node (ref "OK1") (pin "2") (pinfunction "C_2") (pintype "passive"))
      (node (ref "R22") (pin "1") (pinfunction "1_1") (pintype "passive"))
      (node (ref "ZD3") (pin "C") (pinfunction "C_C") (pintype "passive"))
    )
    (net (code "91") (name "Net-(OK2-C)") (class "Default")
      (node (ref "OK2") (pin "2") (pinfunction "C_2") (pintype "passive"))
      (node (ref "R39") (pin "1") (pinfunction "1_1") (pintype "passive"))
    )
    (net (code "92") (name "Net-(OK3-A)") (class "Default")
      (node (ref "OK3") (pin "1") (pinfunction "A_1") (pintype "passive"))
      (node (ref "R76") (pin "1") (pinfunction "1_1") (pintype "passive"))
      (node (ref "R84") (pin "1") (pinfunction "1_1") (pintype "passive"))
    )
    (net (code "93") (name "Net-(Q1-B)") (class "Default")
      (node (ref "C8") (pin "1") (pinfunction "1_1") (pintype "passive"))
      (node (ref "Q1") (pin "1") (pinfunction "B_1") (pintype "passive"))
      (node (ref "R5") (pin "2") (pinfunction "2_2") (pintype "passive"))
      (node (ref "ZD2") (pin "C") (pinfunction "C_C") (pintype "passive"))
    )
    (net (code "94") (name "Net-(Q5-A)") (class "Default")
      (node (ref "D20") (pin "C") (pinfunction "C_C") (pintype "passive"))
      (node (ref "D21") (pin "C") (pinfunction "C_C") (pintype "passive"))
      (node (ref "Q5") (pin "3") (pinfunction "A_3") (pintype "passive"))
    )
    (net (code "95") (name "Net-(Q5-G)") (class "Default")
      (node (ref "Q5") (pin "2") (pinfunction "G_2") (pintype "passive"))
      (node (ref "R49") (pin "1") (pinfunction "1_1") (pintype "passive"))
    )
    (net (code "96") (name "Net-(Q7-PadB)") (class "Default")
      (node (ref "Q7") (pin "B") (pinfunction "B_B") (pintype "passive"))
      (node (ref "R52") (pin "2") (pinfunction "2_2") (pintype "passive"))
      (node (ref "R54") (pin "1") (pinfunction "1_1") (pintype "passive"))
    )
    (net (code "97") (name "Net-(R1-Pad2)") (class "Default")
      (node (ref "R1") (pin "2") (pinfunction "2_2") (pintype "passive"))
      (node (ref "R2") (pin "1") (pinfunction "1_1") (pintype "passive"))
    )
    (net (code "98") (name "Net-(R8-Pad2)") (class "Default")
      (node (ref "R8") (pin "2") (pinfunction "2_2") (pintype "passive"))
      (node (ref "R9") (pin "1") (pinfunction "1_1") (pintype "passive"))
    )
    (net (code "99") (name "Net-(R29-Pad1)") (class "Default")
      (node (ref "R29") (pin "1") (pinfunction "1_1") (pintype "passive"))
      (node (ref "R31") (pin "2") (pinfunction "2_2") (pintype "passive"))
    )
    (net (code "100") (name "Net-(R35-Pad2)") (class "Default")
      (node (ref "R35") (pin "2") (pinfunction "2_2") (pintype "passive"))
      (node (ref "R43") (pin "1") (pinfunction "1_1") (pintype "passive"))
    )
    (net (code "101") (name "Net-(R71-Pad1)") (class "Default")
      (node (ref "R71") (pin "1") (pinfunction "1_1") (pintype "passive"))
      (node (ref "R77") (pin "2") (pinfunction "2_2") (pintype "passive"))
    )
    (net (code "102") (name "Net-(R73-Pad2)") (class "Default")
      (node (ref "R73") (pin "2") (pinfunction "2_2") (pintype "passive"))
      (node (ref "R74") (pin "1") (pinfunction "1_1") (pintype "passive"))
    )
    (net (code "103") (name "Net-(SAR1-P$1)") (class "Default")
      (node (ref "C1") (pin "1") (pinfunction "1_1") (pintype "passive"))
      (node (ref "C2A") (pin "2") (pinfunction "2_2") (pintype "passive"))
      (node (ref "L1") (pin "2") (pinfunction "2_2") (pintype "passive"))
      (node (ref "R1") (pin "1") (pinfunction "1_1") (pintype "passive"))
      (node (ref "SAR1") (pin "1") (pinfunction "P$1_1") (pintype "bidirectional"))
      (node (ref "X2") (pin "2") (pinfunction "1_2") (pintype "passive"))
    )
    (net (code "104") (name "Net-(SAR1-P$2)") (class "Default")
      (node (ref "B1") (pin "AC1") (pinfunction "AC1_AC1") (pintype "passive"))
      (node (ref "C2") (pin "1") (pinfunction "1_1") (pintype "passive"))
      (node (ref "C5") (pin "2") (pinfunction "2_2") (pintype "passive"))
      (node (ref "L1") (pin "1") (pinfunction "1_1") (pintype "passive"))
      (node (ref "SAR1") (pin "2") (pinfunction "P$2_2") (pintype "bidirectional"))
    )
    (net (code "105") (name "Net-(TP5-P$1)") (class "Default")
      (node (ref "C42") (pin "1") (pinfunction "1_1") (pintype "passive"))
      (node (ref "D21") (pin "A") (pinfunction "A_A") (pintype "passive"))
      (node (ref "R43") (pin "2") (pinfunction "2_2") (pintype "passive"))
      (node (ref "R45") (pin "2") (pinfunction "2_2") (pintype "passive"))
      (node (ref "R46") (pin "1") (pinfunction "1_1") (pintype "passive"))
      (node (ref "TP5") (pin "1") (pinfunction "P$1_1") (pintype "bidirectional"))
    )
    (net (code "106") (name "Net-(TR1-P2_DOT)") (class "Default")
      (node (ref "D4") (pin "A") (pinfunction "A_A") (pintype "passive"))
      (node (ref "IC3") (pin "13") (pinfunction "DRAIN_13") (pintype "output"))
      (node (ref "IC3") (pin "14") (pinfunction "DRAIN_14") (pintype "output"))
      (node (ref "IC3") (pin "15") (pinfunction "DRAIN_15") (pintype "output"))
      (node (ref "IC3") (pin "16") (pinfunction "DRAIN_16") (pintype "output"))
      (node (ref "TR1") (pin "4") (pinfunction "P2_DOT_4") (pintype "passive"))
    )
    (net (code "107") (name "Net-(TR1-S2)") (class "Default")
      (node (ref "C18") (pin "2") (pinfunction "2_2") (pintype "passive"))
      (node (ref "D5") (pin "C") (pinfunction "C_C") (pintype "passive"))
      (node (ref "TR1") (pin "8") (pinfunction "S2_8") (pintype "passive"))
    )
    (net (code "108") (name "Net-(TR1-S3_DOT)") (class "Default")
      (node (ref "C9") (pin "2") (pinfunction "2_2") (pintype "passive"))
      (node (ref "D2") (pin "A") (pinfunction "A_A") (pintype "passive"))
      (node (ref "TR1") (pin "15") (pinfunction "S3_DOT_15") (pintype "passive"))
    )
    (net (code "109") (name "Net-(TR2-P_DOT)") (class "Default")
      (node (ref "Q2") (pin "D") (pinfunction "D_D") (pintype "passive"))
      (node (ref "TR2") (pin "8") (pinfunction "P_DOT_8") (pintype "passive"))
    )
    (net (code "110") (name "Net-(TR2-S)") (class "Default")
      (node (ref "D12") (pin "A") (pinfunction "A_A") (pintype "passive"))
      (node (ref "R23") (pin "1") (pinfunction "1_1") (pintype "passive"))
      (node (ref "TR2") (pin "3") (pinfunction "S_3") (pintype "passive"))
    )
    (net (code "111") (name "Net-(X3H-S)") (class "Default")
      (node (ref "C15") (pin "2") (pinfunction "2_2") (pintype "passive"))
      (node (ref "C16") (pin "2") (pinfunction "2_2") (pintype "passive"))
      (node (ref "D6") (pin "A") (pinfunction "A_A") (pintype "passive"))
      (node (ref "IC1") (pin "2") (pinfunction "IN_2") (pintype "input"))
      (node (ref "IC1") (pin "3") (pinfunction "IN_3") (pintype "input"))
      (node (ref "IC1") (pin "6") (pinfunction "IN_6") (pintype "input"))
      (node (ref "IC1") (pin "7") (pinfunction "IN_7") (pintype "input"))
      (node (ref "L3") (pin "2") (pinfunction "2_2") (pintype "passive"))
      (node (ref "X3") (pin "8") (pinfunction "S_8") (pintype "passive"))
    )
    (net (code "112") (name "PE") (class "Default")
      (node (ref "C2A") (pin "1") (pinfunction "1_1") (pintype "passive"))
      (node (ref "C4") (pin "1") (pinfunction "1_1") (pintype "passive"))
      (node (ref "C4A") (pin "1") (pinfunction "1_1") (pintype "passive"))
      (node (ref "C5") (pin "1") (pinfunction "1_1") (pintype "passive"))
      (node (ref "JP2") (pin "NO") (pinfunction "NO_NO") (pintype "passive"))
      (node (ref "X2") (pin "1") (pinfunction "1_1") (pintype "passive"))
    )
    (net (code "113") (name "POUT+") (class "Default")
      (node (ref "C54") (pin "+") (pinfunction "+_+") (pintype "passive"))
      (node (ref "C55") (pin "+") (pinfunction "+_+") (pintype "passive"))
      (node (ref "C56") (pin "+") (pinfunction "+_+") (pintype "passive"))
      (node (ref "C57") (pin "1") (pinfunction "1_1") (pintype "passive"))
      (node (ref "L7") (pin "1") (pinfunction "1_1") (pintype "passive"))
      (node (ref "R60") (pin "1") (pinfunction "1_1") (pintype "passive"))
      (node (ref "R71") (pin "2") (pinfunction "2_2") (pintype "passive"))
      (node (ref "SH2") (pin "P$2") (pinfunction "GND_B_P$2") (pintype "bidirectional"))
      (node (ref "SH3") (pin "P$1") (pinfunction "GND_A_P$1") (pintype "bidirectional"))
    )
    (net (code "114") (name "PREG_OUT+") (class "Default")
      (node (ref "C58") (pin "1") (pinfunction "1_1") (pintype "passive"))
      (node (ref "C59") (pin "1") (pinfunction "1_1") (pintype "passive"))
      (node (ref "C60") (pin "1") (pinfunction "1_1") (pintype "passive"))
      (node (ref "C61") (pin "1") (pinfunction "1_1") (pintype "passive"))
      (node (ref "JP1") (pin "NC") (pinfunction "NC_NC") (pintype "passive"))
      (node (ref "L7") (pin "2") (pinfunction "2_2") (pintype "passive"))
      (node (ref "R60") (pin "2") (pinfunction "2_2") (pintype "passive"))
      (node (ref "R61") (pin "2") (pinfunction "2_2") (pintype "passive"))
      (node (ref "TP7") (pin "TIP") (pinfunction "TIP_TIP") (pintype "bidirectional"))
      (node (ref "X3") (pin "2") (pinfunction "S_2") (pintype "passive"))
      (node (ref "X5") (pin "1") (pinfunction "1_1") (pintype "passive"))
      (node (ref "ZD6") (pin "C") (pinfunction "C_C") (pintype "passive"))
    )
    (net (code "115") (name "PULL") (class "Default")
      (node (ref "D23") (pin "A") (pinfunction "A_A") (pintype "passive"))
      (node (ref "IC5") (pin "9") (pinfunction "PULL_9") (pintype "output"))
      (node (ref "R48") (pin "2") (pinfunction "2_2") (pintype "passive"))
    )
    (net (code "116") (name "PUSH") (class "Default")
      (node (ref "D22") (pin "A") (pinfunction "A_A") (pintype "passive"))
      (node (ref "IC5") (pin "8") (pinfunction "PUSH_8") (pintype "output"))
      (node (ref "R47") (pin "2") (pinfunction "2_2") (pintype "passive"))
    )
    (net (code "117") (name "PWRGOOD") (class "Default")
      (node (ref "IC2") (pin "5") (pinfunction "~{ERROR}_5") (pintype "input"))
      (node (ref "OK2") (pin "4") (pinfunction "COL_4") (pintype "passive"))
      (node (ref "R15") (pin "2") (pinfunction "2_2") (pintype "passive"))
      (node (ref "X3") (pin "4") (pinfunction "S_4") (pintype "passive"))
    )
    (net (code "118") (name "REF") (class "Default")
      (node (ref "C37") (pin "2") (pinfunction "2_2") (pintype "passive"))
      (node (ref "IC4") (pin "3") (pinfunction "VDDI_3") (pintype "power_in"))
      (node (ref "IC4") (pin "8") (pinfunction "VDDI_8") (pintype "power_in"))
      (node (ref "R36") (pin "2") (pinfunction "2_2") (pintype "passive"))
      (node (ref "ZD4") (pin "C") (pinfunction "C_C") (pintype "passive"))
    )
    (net (code "119") (name "S1_DOT_OUT") (class "Default")
      (node (ref "IC7") (pin "4") (pinfunction "VD1_4") (pintype "passive"))
      (node (ref "Q8") (pin "3") (pinfunction "D_3") (pintype "passive"))
      (node (ref "R62") (pin "1") (pinfunction "1_1") (pintype "passive"))
      (node (ref "R63") (pin "1") (pinfunction "1_1") (pintype "passive"))
      (node (ref "TR3") (pin "S1_DOT") (pinfunction "S1_DOT_S1_DOT") (pintype "passive"))
    )
    (net (code "120") (name "S1_OUT") (class "Default")
      (node (ref "SH2") (pin "P$1") (pinfunction "GND_A_P$1") (pintype "bidirectional"))
      (node (ref "TR3") (pin "S1") (pinfunction "S1_S1") (pintype "passive"))
    )
    (net (code "121") (name "S2_DOT_OUT") (class "Default")
      (node (ref "SH3") (pin "P$2") (pinfunction "GND_B_P$2") (pintype "bidirectional"))
      (node (ref "TR3") (pin "S2_DOT") (pinfunction "S2_DOT_S2_DOT") (pintype "passive"))
    )
    (net (code "122") (name "S2_OUT") (class "Default")
      (node (ref "IC7") (pin "5") (pinfunction "VD2_5") (pintype "passive"))
      (node (ref "Q9") (pin "3") (pinfunction "D_3") (pintype "passive"))
      (node (ref "R68") (pin "1") (pinfunction "1_1") (pintype "passive"))
      (node (ref "R69") (pin "1") (pinfunction "1_1") (pintype "passive"))
      (node (ref "TR3") (pin "S2") (pinfunction "S2_S2") (pintype "passive"))
    )
    (net (code "123") (name "SR_OUT1") (class "Default")
      (node (ref "D24") (pin "A") (pinfunction "A_A") (pintype "passive"))
      (node (ref "Q8") (pin "1") (pinfunction "G_1") (pintype "passive"))
      (node (ref "R64") (pin "1") (pinfunction "1_1") (pintype "passive"))
    )
    (net (code "124") (name "SR_OUT2") (class "Default")
      (node (ref "D25") (pin "A") (pinfunction "A_A") (pintype "passive"))
      (node (ref "Q9") (pin "1") (pinfunction "G_1") (pintype "passive"))
      (node (ref "R67") (pin "1") (pinfunction "1_1") (pintype "passive"))
    )
    (net (code "125") (name "U_MON") (class "Default")
      (node (ref "JP4") (pin "NC") (pinfunction "NC_NC") (pintype "passive"))
      (node (ref "X3") (pin "1") (pinfunction "S_1") (pintype "passive"))
    )
    (net (code "126") (name "V+") (class "Default")
      (node (ref "C23") (pin "+") (pinfunction "+_+") (pintype "passive"))
      (node (ref "C66") (pin "1") (pinfunction "1_1") (pintype "passive"))
      (node (ref "C69") (pin "1") (pinfunction "1_1") (pintype "passive"))
      (node (ref "D7") (pin "A") (pinfunction "A_A") (pintype "passive"))
      (node (ref "D9") (pin "C") (pinfunction "C_C") (pintype "passive"))
      (node (ref "IC2") (pin "1") (pinfunction "OUT_1") (pintype "output"))
      (node (ref "IC8") (pin "8") (pinfunction "V+_8") (pintype "power_in"))
      (node (ref "IC9") (pin "8") (pinfunction "VCC+_8") (pintype "power_in"))
      (node (ref "R12") (pin "1") (pinfunction "1_1") (pintype "passive"))
      (node (ref "R15") (pin "1") (pinfunction "1_1") (pintype "passive"))
      (node (ref "R76") (pin "2") (pinfunction "2_2") (pintype "passive"))
      (node (ref "R78") (pin "2") (pinfunction "2_2") (pintype "passive"))
      (node (ref "X3") (pin "5") (pinfunction "S_5") (pintype "passive"))
    )
    (net (code "127") (name "V-") (class "Default")
      (node (ref "C17") (pin "2") (pinfunction "2_2") (pintype "passive"))
      (node (ref "C68") (pin "1") (pinfunction "1_1") (pintype "passive"))
      (node (ref "D3") (pin "A") (pinfunction "A_A") (pintype "passive"))
      (node (ref "D6") (pin "C") (pinfunction "C_C") (pintype "passive"))
      (node (ref "IC1") (pin "1") (pinfunction "OUT_1") (pintype "passive"))
      (node (ref "IC8") (pin "4") (pinfunction "V-_4") (pintype "power_in"))
      (node (ref "X3") (pin "7") (pinfunction "S_7") (pintype "passive"))
    )
    (net (code "128") (name "unconnected-(IC2-SD-Pad3)") (class "Default")
      (node (ref "IC2") (pin "3") (pinfunction "SD_3") (pintype "input"))
    )
    (net (code "129") (name "unconnected-(IC2-SENSE-Pad2)") (class "Default")
      (node (ref "IC2") (pin "2") (pinfunction "SENSE_2") (pintype "input"))
    )
    (net (code "130") (name "unconnected-(IC2-VTAP-Pad6)") (class "Default")
      (node (ref "IC2") (pin "6") (pinfunction "VTAP_6") (pintype "input"))
    )
  )
)
